# On_Board_Computer.net
KiCad netlist of a schematic drawn in EAGLE
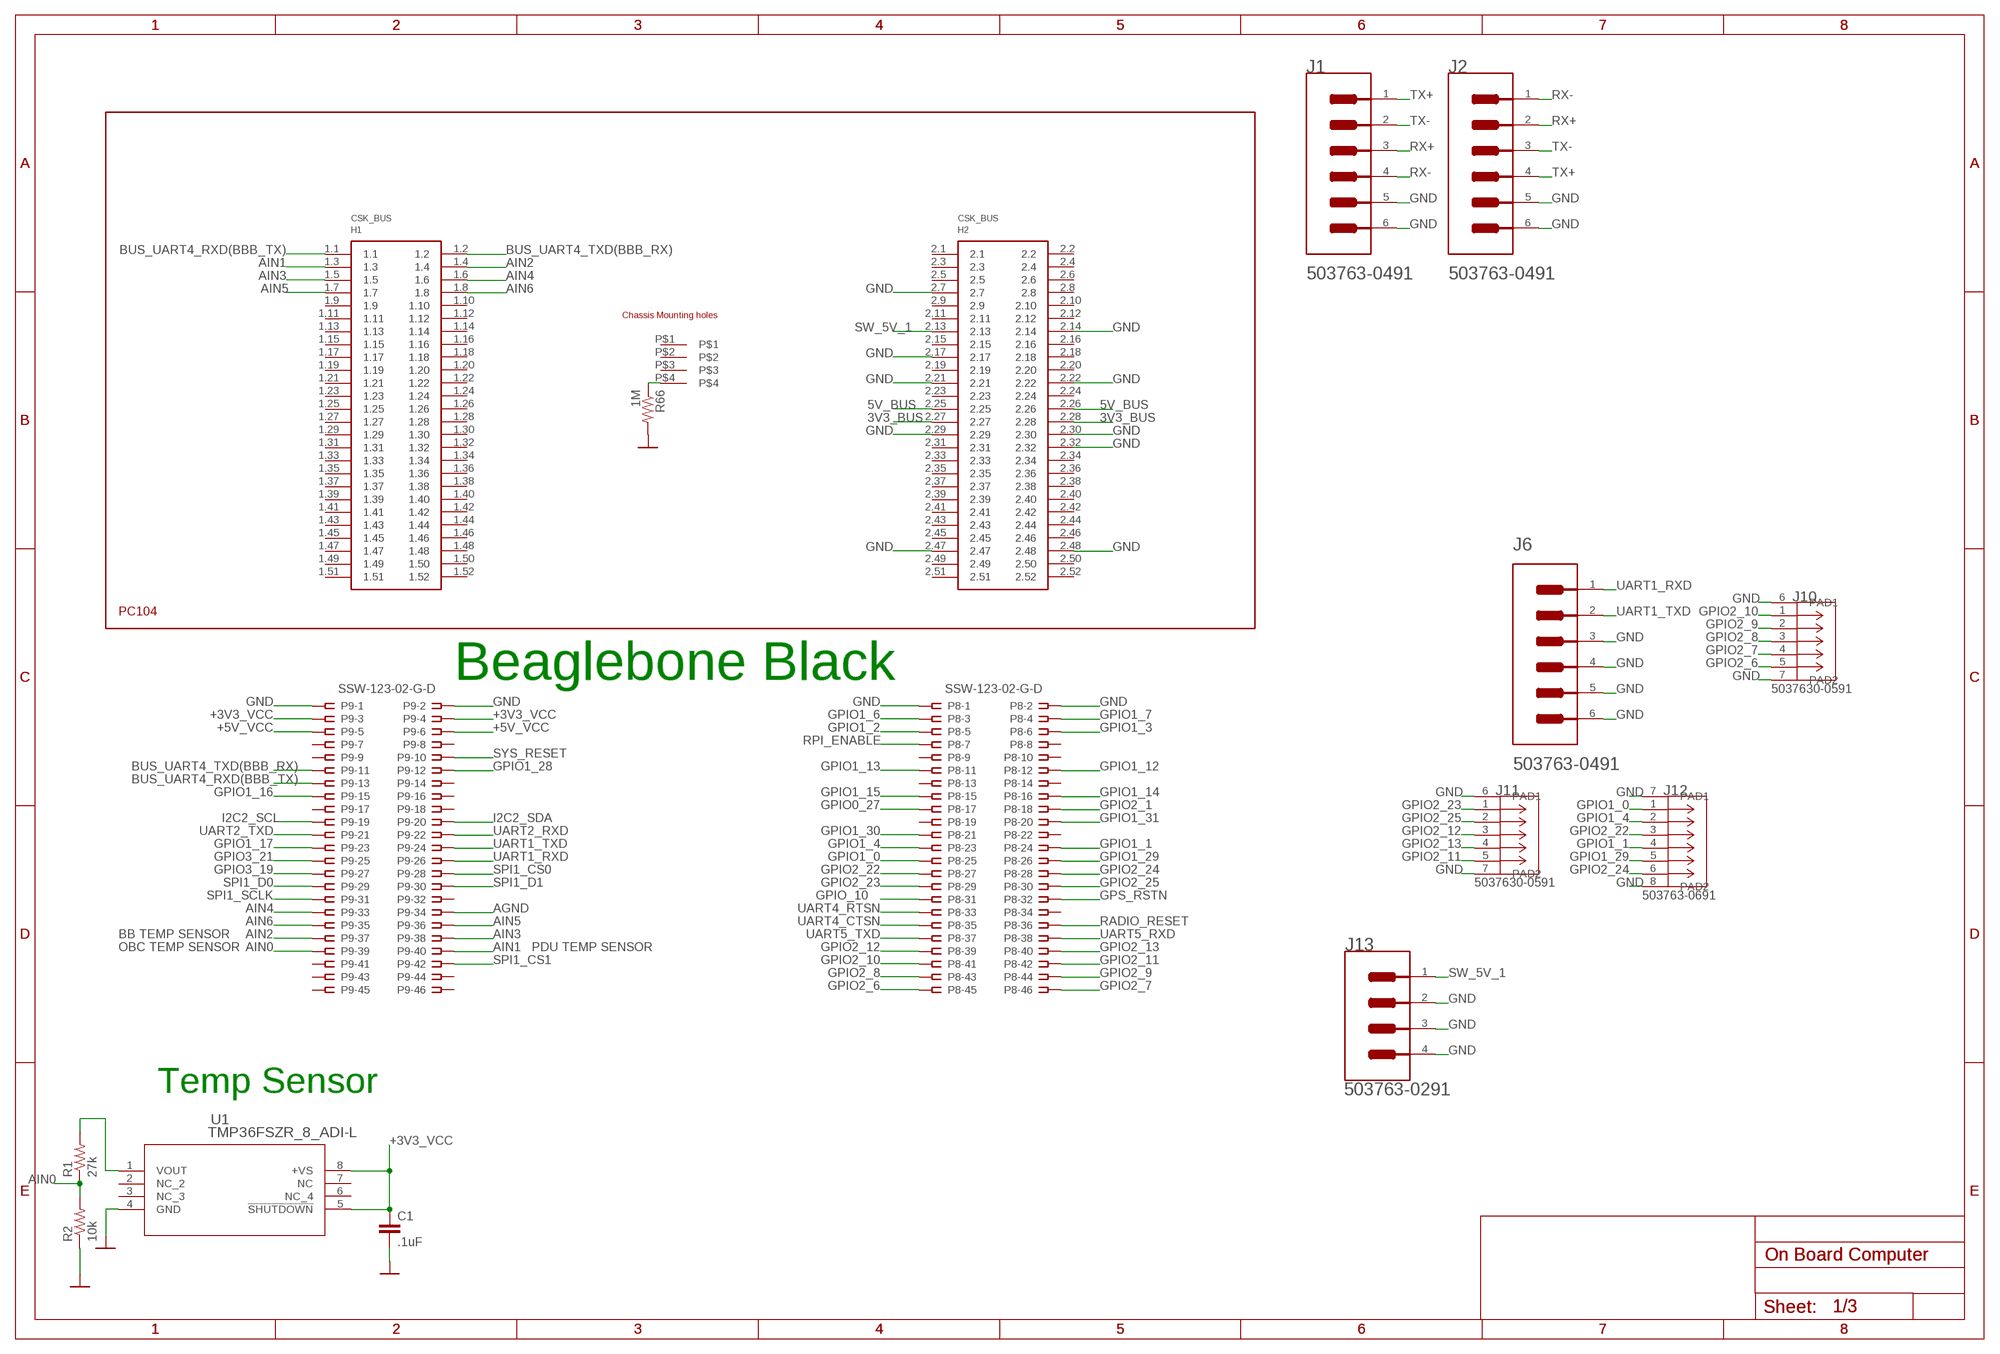
[diagram p0: schematic, sheet 1]
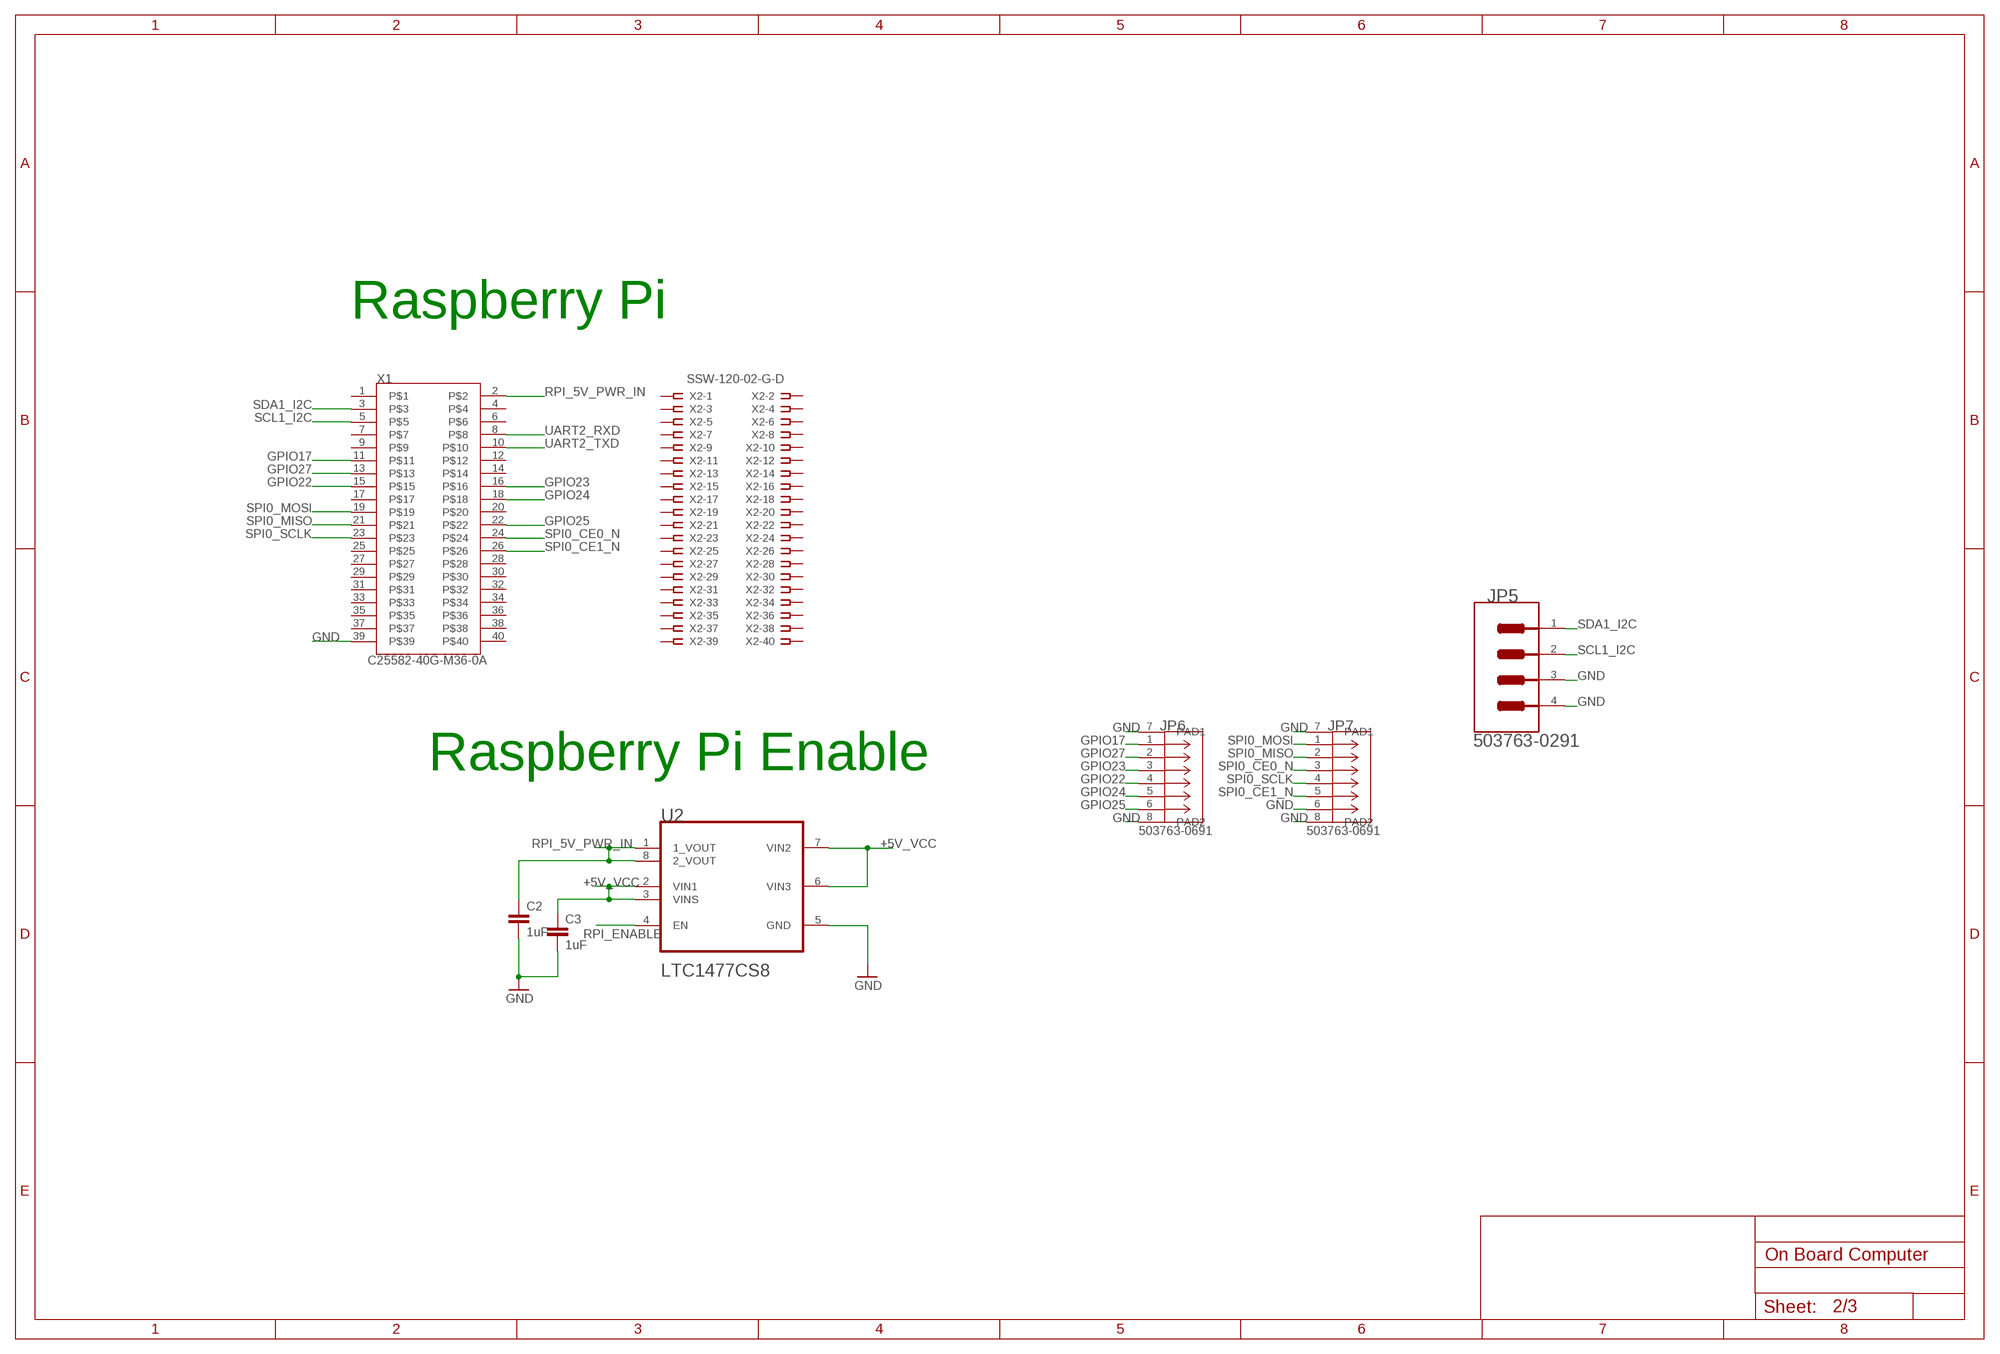
[diagram p1: schematic, sheet 2]
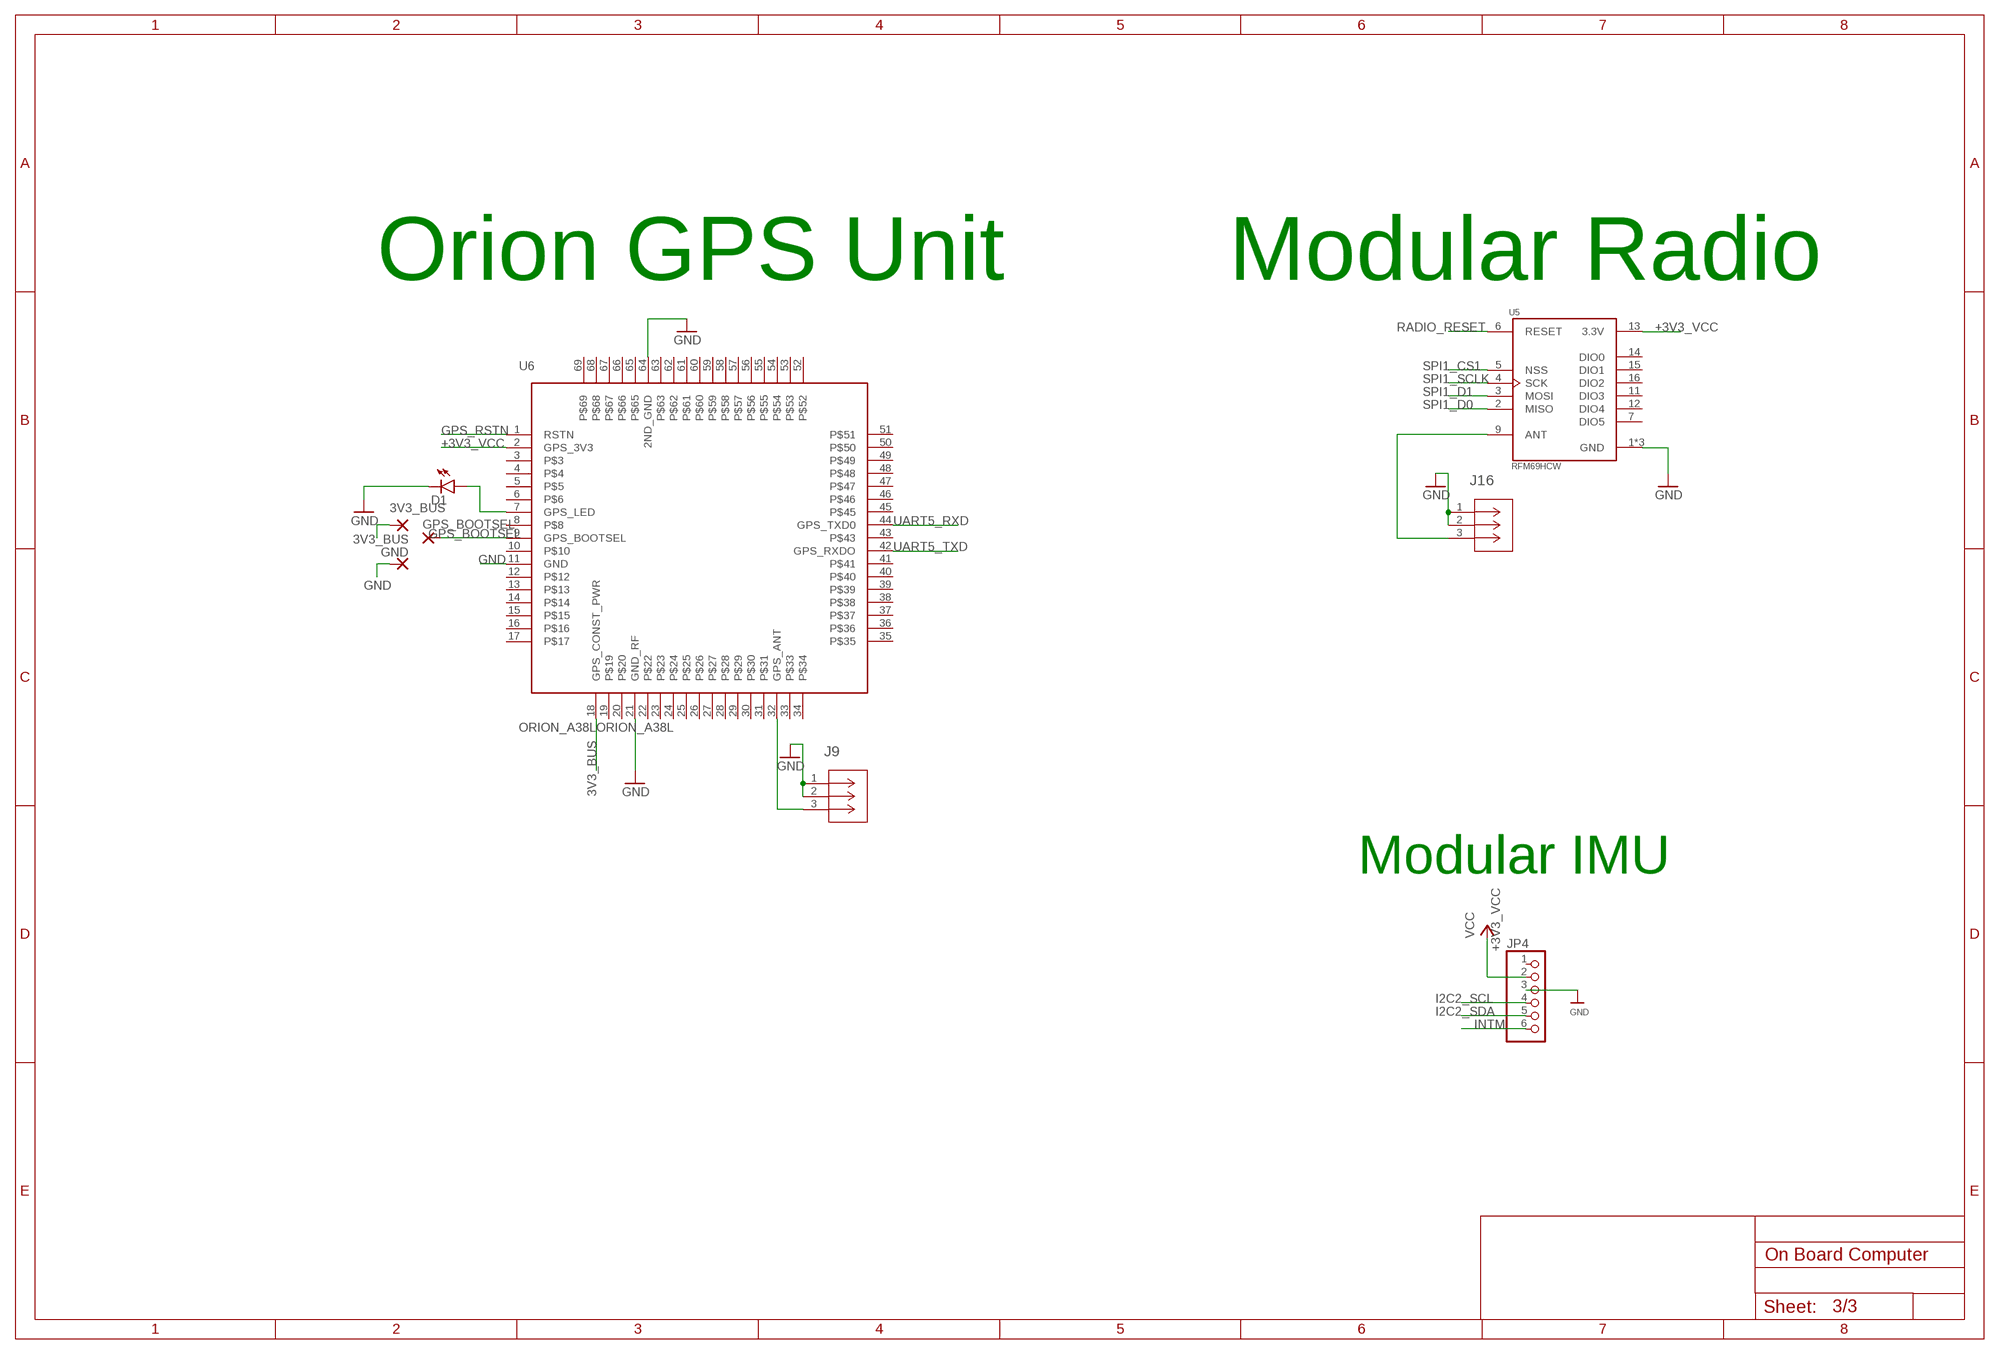
[diagram p2: schematic, sheet 3]

(export (version "E")
  (design (tool "Eeschema 10.0.6"))
  (components
    (comp (ref "C1")
      (value ".1uF")
      (footprint "eagle-import:0805")
      (libsource (lib "eagle-import") (part "CAP0805"))
    )
    (comp (ref "H1")
      (value "PC104_WCONN")
      (footprint "eagle-import:PC104_WCONN")
      (libsource (lib "eagle-import") (part "PC104_WCONN"))
    )
    (comp (ref "J1")
      (value "MOLEX_503763-0491MOLEX_503763-0491_0_0")
      (footprint "eagle-import:MOLEX_503763-0491_0")
      (fields
        (field (name "DIGIKEY_PART_NUMBER") "WM10655CT-ND")
        (field (name "MF") "Molex")
        (field (name "MOUSER_PART_NUMBER") "538-503763-0491")
      )
      (libsource (lib "eagle-import") (part "MOLEX_503763-0491MOLEX_503763-0491_0_0"))
    )
    (comp (ref "J2")
      (value "MOLEX_503763-0491MOLEX_503763-0491_0_0")
      (footprint "eagle-import:MOLEX_503763-0491_0")
      (fields
        (field (name "DIGIKEY_PART_NUMBER") "WM10655CT-ND")
        (field (name "MF") "Molex")
        (field (name "MOUSER_PART_NUMBER") "538-503763-0491")
      )
      (libsource (lib "eagle-import") (part "MOLEX_503763-0491MOLEX_503763-0491_0_0"))
    )
    (comp (ref "J6")
      (value "MOLEX_503763-0491MOLEX_503763-0491_0_0")
      (footprint "eagle-import:MOLEX_503763-0491_0")
      (fields
        (field (name "DIGIKEY_PART_NUMBER") "WM10655CT-ND")
        (field (name "MF") "Molex")
        (field (name "MOUSER_PART_NUMBER") "538-503763-0491")
      )
      (libsource (lib "eagle-import") (part "MOLEX_503763-0491MOLEX_503763-0491_0_0"))
    )
    (comp (ref "J10")
      (value "503763-0591")
      (footprint "eagle-import:CONN_5037630591_MOL")
      (fields (field (name "COPYRIGHT") "Copyright (C) 2018 Accelerated Designs. All rights reserved"))
      (libsource (lib "eagle-import") (part "503763-0591"))
    )
    (comp (ref "J11")
      (value "503763-0591")
      (footprint "eagle-import:CONN_5037630591_MOL")
      (fields (field (name "COPYRIGHT") "Copyright (C) 2018 Accelerated Designs. All rights reserved"))
      (libsource (lib "eagle-import") (part "503763-0591"))
    )
    (comp (ref "J12")
      (value "503763-0691")
      (footprint "eagle-import:CONN_503763-0691_MOL")
      (fields (field (name "COPYRIGHT") "Copyright (C) 2018 Accelerated Designs. All rights reserved"))
      (libsource (lib "eagle-import") (part "503763-0691"))
    )
    (comp (ref "J13")
      (value "MOLEX_503763-0291MOLEX_503763-0291_0_0")
      (footprint "eagle-import:MOLEX_503763-0291_0")
      (fields
        (field (name "DIGIKEY_PART_NUMBER") "WM10654CT-ND")
        (field (name "MF") "Molex")
        (field (name "MOUSER_PART_NUMBER") "538-503763-0291")
      )
      (libsource (lib "eagle-import") (part "MOLEX_503763-0291MOLEX_503763-0291_0_0"))
    )
    (comp (ref "P8")
      (value "SSW-123-02-G-D")
      (footprint "eagle-import:SSW-123-02-G-D")
      (fields (field (name "MF") "Samtec Inc."))
      (libsource (lib "eagle-import") (part "SSW-123-02-G-D"))
    )
    (comp (ref "P9")
      (value "SSW-123-02-G-D")
      (footprint "eagle-import:SSW-123-02-G-D")
      (fields (field (name "MF") "Samtec Inc."))
      (libsource (lib "eagle-import") (part "SSW-123-02-G-D"))
    )
    (comp (ref "R1")
      (value "27k")
      (footprint "eagle-import:0805")
      (libsource (lib "eagle-import") (part "RESISTOR0805-RES"))
    )
    (comp (ref "R2")
      (value "10k")
      (footprint "eagle-import:0805")
      (libsource (lib "eagle-import") (part "RESISTOR0805-RES"))
    )
    (comp (ref "R66")
      (value "1M")
      (footprint "eagle-import:0805")
      (libsource (lib "eagle-import") (part "RESISTOR0805-RES"))
    )
    (comp (ref "U1")
      (value "TMP36FSZR_8_ADI-L")
      (footprint "eagle-import:R_8_ADI-L")
      (fields
        (field (name "MANUFACTURER_PART_NUMBER") "TMP36FSZ")
        (field (name "COPYRIGHT") "Copyright (C) 2021 Ultra Librarian. All rights reserved.")
      )
      (libsource (lib "eagle-import") (part "TMP36FSZR_8_ADI-L"))
    )
    (comp (ref "3V3_BUS")
      (value "1,6/0,9")
      (footprint "eagle-import:1,6_0,9")
      (libsource (lib "eagle-import") (part "1,6/0,9"))
    )
    (comp (ref "D1")
      (value "LEDCHIP-LED0603")
      (footprint "eagle-import:CHIP-LED0603")
      (libsource (lib "eagle-import") (part "LEDCHIP-LED0603"))
    )
    (comp (ref "GND")
      (value "GND")
      (footprint "eagle-import:1,6_0,9")
      (libsource (lib "eagle-import") (part "1,6/0,9"))
    )
    (comp (ref "GPS_BOOTSEL")
      (value "1,6/0,9")
      (footprint "eagle-import:1,6_0,9")
      (libsource (lib "eagle-import") (part "1,6/0,9"))
    )
    (comp (ref "J9")
      (value "U.FL-R-SMT-1(01)")
      (footprint "eagle-import:CONN_-SMT-1(01)")
      (fields (field (name "COPYRIGHT") "Copyright (C) 2018 Accelerated Designs. All rights reserved"))
      (libsource (lib "eagle-import") (part "U.FL-R-SMT-1(01)"))
    )
    (comp (ref "J16")
      (value "U.FL-R-SMT-1(01)")
      (footprint "eagle-import:CONN_-SMT-1(01)")
      (fields (field (name "COPYRIGHT") "Copyright (C) 2018 Accelerated Designs. All rights reserved"))
      (libsource (lib "eagle-import") (part "U.FL-R-SMT-1(01)"))
    )
    (comp (ref "JP4")
      (value "HEADER-1X670MIL")
      (footprint "eagle-import:1X06_ROUND_70")
      (libsource (lib "eagle-import") (part "HEADER-1X670MIL"))
    )
    (comp (ref "U5")
      (value "RFM69HCW")
      (footprint "eagle-import:RFM69HCW")
      (fields (field (name "MF") "HOPERF") (field (name "MP") "RFM69HCW-315S2"))
      (libsource (lib "eagle-import") (part "RFM69HCW"))
    )
    (comp (ref "U6")
      (value "ORION_A38LORION_A38L")
      (footprint "eagle-import:ORION_A38L")
      (libsource (lib "eagle-import") (part "ORION_A38LORION_A38L"))
    )
    (comp (ref "C2")
      (value "1uF")
      (footprint "eagle-import:0805")
      (libsource (lib "eagle-import") (part "CAP0805"))
    )
    (comp (ref "C3")
      (value "1uF")
      (footprint "eagle-import:0805")
      (libsource (lib "eagle-import") (part "CAP0805"))
    )
    (comp (ref "JP5")
      (value "MOLEX_503763-0291MOLEX_503763-0291_0_0")
      (footprint "eagle-import:MOLEX_503763-0291_0")
      (fields
        (field (name "DIGIKEY_PART_NUMBER") "WM10654CT-ND")
        (field (name "MF") "Molex")
        (field (name "MOUSER_PART_NUMBER") "538-503763-0291")
      )
      (libsource (lib "eagle-import") (part "MOLEX_503763-0291MOLEX_503763-0291_0_0"))
    )
    (comp (ref "JP6")
      (value "503763-0691")
      (footprint "eagle-import:CONN_503763-0691_MOL")
      (fields (field (name "COPYRIGHT") "Copyright (C) 2018 Accelerated Designs. All rights reserved"))
      (libsource (lib "eagle-import") (part "503763-0691"))
    )
    (comp (ref "JP7")
      (value "503763-0691")
      (footprint "eagle-import:CONN_503763-0691_MOL")
      (fields (field (name "COPYRIGHT") "Copyright (C) 2018 Accelerated Designs. All rights reserved"))
      (libsource (lib "eagle-import") (part "503763-0691"))
    )
    (comp (ref "U2")
      (value "LTC1477CS8LINEAR_TECHNOLOGY_LTC1477CS8_0_2")
      (footprint "eagle-import:LINEAR_TECHNOLOGY_LTC1477CS8_2")
      (fields (field (name "MF") "Linear Technology") (field (name "MPN") "LTC1477CS8"))
      (libsource (lib "eagle-import") (part "LTC1477CS8LINEAR_TECHNOLOGY_LTC1477CS8_0_2"))
    )
    (comp (ref "X1")
      (value "C25582-40G-M36-0A")
      (footprint "eagle-import:ADAFRUIT_C25582-40G-M36-0A_0")
      (libsource (lib "eagle-import") (part "C25582-40G-M36-0A"))
    )
    (comp (ref "X2")
      (value "SSW-120-02-G-D")
      (footprint "eagle-import:SSW-120-02-G-D")
      (fields (field (name "MF") "Samtec Inc."))
      (libsource (lib "eagle-import") (part "SSW-120-02-G-D"))
    )
  )
  (nets
    (net (code "1") (name "+3V3_VCC") (class "Default")
      (node (ref "C1") (pin "1") (pinfunction "1_1") (pintype "passive"))
      (node (ref "JP4") (pin "2") (pinfunction "2_2") (pintype "passive"))
      (node (ref "P9") (pin "3") (pinfunction "1_3") (pintype "passive"))
      (node (ref "P9") (pin "4") (pinfunction "1_4") (pintype "passive"))
      (node (ref "U1") (pin "5") (pinfunction "~{SHUTDOWN}_5") (pintype "passive"))
      (node (ref "U1") (pin "8") (pinfunction "+VS_8") (pintype "power_in"))
      (node (ref "U5") (pin "13") (pinfunction "3.3V_13") (pintype "power_in"))
      (node (ref "U6") (pin "2") (pinfunction "GPS_3V3_2") (pintype "bidirectional"))
    )
    (net (code "2") (name "+5V_VCC") (class "Default")
      (node (ref "C3") (pin "1") (pinfunction "1_1") (pintype "passive"))
      (node (ref "P9") (pin "5") (pinfunction "1_5") (pintype "passive"))
      (node (ref "P9") (pin "6") (pinfunction "1_6") (pintype "passive"))
      (node (ref "U2") (pin "2") (pinfunction "VIN1_2") (pintype "power_in"))
      (node (ref "U2") (pin "3") (pinfunction "VINS_3") (pintype "power_in"))
      (node (ref "U2") (pin "6") (pinfunction "VIN3_6") (pintype "power_in"))
      (node (ref "U2") (pin "7") (pinfunction "VIN2_7") (pintype "power_in"))
    )
    (net (code "3") (name "3V3_BUS") (class "Default")
      (node (ref "3V3_BUS") (pin "1") (pinfunction "P_1") (pintype "passive"))
      (node (ref "H1") (pin "2.27") (pinfunction "2.27_2.27") (pintype "bidirectional"))
      (node (ref "H1") (pin "2.28") (pinfunction "2.28_2.28") (pintype "bidirectional"))
      (node (ref "U6") (pin "18") (pinfunction "GPS_CONST_PWR_18") (pintype "bidirectional"))
    )
    (net (code "4") (name "5V_BUS") (class "Default")
      (node (ref "H1") (pin "2.25") (pinfunction "2.25_2.25") (pintype "bidirectional"))
      (node (ref "H1") (pin "2.26") (pinfunction "2.26_2.26") (pintype "bidirectional"))
    )
    (net (code "5") (name "AGND") (class "Default")
      (node (ref "P9") (pin "34") (pinfunction "1_34") (pintype "passive"))
    )
    (net (code "6") (name "AIN0") (class "Default")
      (node (ref "P9") (pin "39") (pinfunction "1_39") (pintype "passive"))
      (node (ref "R1") (pin "1") (pinfunction "1_1") (pintype "passive"))
      (node (ref "R2") (pin "2") (pinfunction "2_2") (pintype "passive"))
    )
    (net (code "7") (name "AIN1") (class "Default")
      (node (ref "H1") (pin "1.3") (pinfunction "1.3_1.3") (pintype "bidirectional"))
      (node (ref "P9") (pin "40") (pinfunction "1_40") (pintype "passive"))
    )
    (net (code "8") (name "AIN2") (class "Default")
      (node (ref "H1") (pin "1.4") (pinfunction "1.4_1.4") (pintype "bidirectional"))
      (node (ref "P9") (pin "37") (pinfunction "1_37") (pintype "passive"))
    )
    (net (code "9") (name "AIN3") (class "Default")
      (node (ref "H1") (pin "1.5") (pinfunction "1.5_1.5") (pintype "bidirectional"))
      (node (ref "P9") (pin "38") (pinfunction "1_38") (pintype "passive"))
    )
    (net (code "10") (name "AIN4") (class "Default")
      (node (ref "H1") (pin "1.6") (pinfunction "1.6_1.6") (pintype "bidirectional"))
      (node (ref "P9") (pin "33") (pinfunction "1_33") (pintype "passive"))
    )
    (net (code "11") (name "AIN5") (class "Default")
      (node (ref "H1") (pin "1.7") (pinfunction "1.7_1.7") (pintype "bidirectional"))
      (node (ref "P9") (pin "36") (pinfunction "1_36") (pintype "passive"))
    )
    (net (code "12") (name "AIN6") (class "Default")
      (node (ref "H1") (pin "1.8") (pinfunction "1.8_1.8") (pintype "bidirectional"))
      (node (ref "P9") (pin "35") (pinfunction "1_35") (pintype "passive"))
    )
    (net (code "13") (name "BUS_UART4_RXD(BBB_TX)") (class "Default")
      (node (ref "H1") (pin "1.1") (pinfunction "1.1_1.1") (pintype "bidirectional"))
      (node (ref "P9") (pin "13") (pinfunction "1_13") (pintype "passive"))
    )
    (net (code "14") (name "BUS_UART4_TXD(BBB_RX)") (class "Default")
      (node (ref "H1") (pin "1.2") (pinfunction "1.2_1.2") (pintype "bidirectional"))
      (node (ref "P9") (pin "11") (pinfunction "1_11") (pintype "passive"))
    )
    (net (code "15") (name "GND") (class "Default")
      (node (ref "C1") (pin "2") (pinfunction "2_2") (pintype "passive"))
      (node (ref "C2") (pin "2") (pinfunction "2_2") (pintype "passive"))
      (node (ref "C3") (pin "2") (pinfunction "2_2") (pintype "passive"))
      (node (ref "D1") (pin "C") (pinfunction "C_C") (pintype "passive"))
      (node (ref "GND") (pin "1") (pinfunction "P_1") (pintype "passive"))
      (node (ref "H1") (pin "2.14") (pinfunction "2.14_2.14") (pintype "bidirectional"))
      (node (ref "H1") (pin "2.17") (pinfunction "2.17_2.17") (pintype "bidirectional"))
      (node (ref "H1") (pin "2.21") (pinfunction "2.21_2.21") (pintype "bidirectional"))
      (node (ref "H1") (pin "2.22") (pinfunction "2.22_2.22") (pintype "bidirectional"))
      (node (ref "H1") (pin "2.29") (pinfunction "2.29_2.29") (pintype "bidirectional"))
      (node (ref "H1") (pin "2.30") (pinfunction "2.30_2.30") (pintype "bidirectional"))
      (node (ref "H1") (pin "2.32") (pinfunction "2.32_2.32") (pintype "bidirectional"))
      (node (ref "H1") (pin "2.47") (pinfunction "2.47_2.47") (pintype "bidirectional"))
      (node (ref "H1") (pin "2.48") (pinfunction "2.48_2.48") (pintype "bidirectional"))
      (node (ref "H1") (pin "2.7") (pinfunction "2.7_2.7") (pintype "bidirectional"))
      (node (ref "J1") (pin "5") (pinfunction "MNT_1_5") (pintype "passive"))
      (node (ref "J1") (pin "6") (pinfunction "MNT_2_6") (pintype "passive"))
      (node (ref "J10") (pin "6") (pinfunction "PAD1_6") (pintype "bidirectional"))
      (node (ref "J10") (pin "7") (pinfunction "PAD2_7") (pintype "bidirectional"))
      (node (ref "J11") (pin "6") (pinfunction "PAD1_6") (pintype "bidirectional"))
      (node (ref "J11") (pin "7") (pinfunction "PAD2_7") (pintype "bidirectional"))
      (node (ref "J12") (pin "7") (pinfunction "PAD1_7") (pintype "bidirectional"))
      (node (ref "J12") (pin "8") (pinfunction "PAD2_8") (pintype "bidirectional"))
      (node (ref "J13") (pin "2") (pinfunction "2_2") (pintype "bidirectional"))
      (node (ref "J13") (pin "3") (pinfunction "MNT_1_3") (pintype "bidirectional"))
      (node (ref "J13") (pin "4") (pinfunction "MNT_2_4") (pintype "bidirectional"))
      (node (ref "J16") (pin "1") (pinfunction "1_1") (pintype "passive"))
      (node (ref "J16") (pin "2") (pinfunction "2_2") (pintype "passive"))
      (node (ref "J2") (pin "5") (pinfunction "MNT_1_5") (pintype "passive"))
      (node (ref "J2") (pin "6") (pinfunction "MNT_2_6") (pintype "passive"))
      (node (ref "J6") (pin "3") (pinfunction "3_3") (pintype "passive"))
      (node (ref "J6") (pin "4") (pinfunction "4_4") (pintype "passive"))
      (node (ref "J6") (pin "5") (pinfunction "MNT_1_5") (pintype "passive"))
      (node (ref "J6") (pin "6") (pinfunction "MNT_2_6") (pintype "passive"))
      (node (ref "J9") (pin "1") (pinfunction "1_1") (pintype "passive"))
      (node (ref "J9") (pin "2") (pinfunction "2_2") (pintype "passive"))
      (node (ref "JP4") (pin "3") (pinfunction "3_3") (pintype "passive"))
      (node (ref "JP5") (pin "3") (pinfunction "MNT_1_3") (pintype "bidirectional"))
      (node (ref "JP5") (pin "4") (pinfunction "MNT_2_4") (pintype "bidirectional"))
      (node (ref "JP6") (pin "7") (pinfunction "PAD1_7") (pintype "bidirectional"))
      (node (ref "JP6") (pin "8") (pinfunction "PAD2_8") (pintype "bidirectional"))
      (node (ref "JP7") (pin "6") (pinfunction "6_6") (pintype "passive"))
      (node (ref "JP7") (pin "7") (pinfunction "PAD1_7") (pintype "bidirectional"))
      (node (ref "JP7") (pin "8") (pinfunction "PAD2_8") (pintype "bidirectional"))
      (node (ref "P8") (pin "1") (pinfunction "1_1") (pintype "passive"))
      (node (ref "P8") (pin "2") (pinfunction "1_2") (pintype "passive"))
      (node (ref "P9") (pin "1") (pinfunction "1_1") (pintype "passive"))
      (node (ref "P9") (pin "2") (pinfunction "1_2") (pintype "passive"))
      (node (ref "R2") (pin "1") (pinfunction "1_1") (pintype "passive"))
      (node (ref "R66") (pin "2") (pinfunction "2_2") (pintype "passive"))
      (node (ref "U1") (pin "4") (pinfunction "GND_4") (pintype "passive"))
      (node (ref "U2") (pin "5") (pinfunction "GND_5") (pintype "power_in"))
      (node (ref "U5") (pin "1") (pinfunction "GND_1") (pintype "power_in"))
      (node (ref "U5") (pin "10") (pinfunction "GND_10") (pintype "power_in"))
      (node (ref "U5") (pin "8") (pinfunction "GND_8") (pintype "power_in"))
      (node (ref "U6") (pin "11") (pinfunction "GND_11") (pintype "bidirectional"))
      (node (ref "U6") (pin "21") (pinfunction "GND_RF_21") (pintype "bidirectional"))
      (node (ref "U6") (pin "64") (pinfunction "2ND_GND_64") (pintype "bidirectional"))
      (node (ref "X1") (pin "39") (pinfunction "P$39_39") (pintype "bidirectional"))
    )
    (net (code "16") (name "GPIO0_27") (class "Default")
      (node (ref "P8") (pin "17") (pinfunction "1_17") (pintype "passive"))
    )
    (net (code "17") (name "GPIO1_0") (class "Default")
      (node (ref "J12") (pin "1") (pinfunction "1_1") (pintype "passive"))
      (node (ref "P8") (pin "25") (pinfunction "1_25") (pintype "passive"))
    )
    (net (code "18") (name "GPIO1_1") (class "Default")
      (node (ref "J12") (pin "4") (pinfunction "4_4") (pintype "passive"))
      (node (ref "P8") (pin "24") (pinfunction "1_24") (pintype "passive"))
    )
    (net (code "19") (name "GPIO1_2") (class "Default")
      (node (ref "P8") (pin "5") (pinfunction "1_5") (pintype "passive"))
    )
    (net (code "20") (name "GPIO1_3") (class "Default")
      (node (ref "P8") (pin "6") (pinfunction "1_6") (pintype "passive"))
    )
    (net (code "21") (name "GPIO1_4") (class "Default")
      (node (ref "J12") (pin "2") (pinfunction "2_2") (pintype "passive"))
      (node (ref "P8") (pin "23") (pinfunction "1_23") (pintype "passive"))
    )
    (net (code "22") (name "GPIO1_6") (class "Default")
      (node (ref "P8") (pin "3") (pinfunction "1_3") (pintype "passive"))
    )
    (net (code "23") (name "GPIO1_7") (class "Default")
      (node (ref "P8") (pin "4") (pinfunction "1_4") (pintype "passive"))
    )
    (net (code "24") (name "GPIO1_12") (class "Default")
      (node (ref "P8") (pin "12") (pinfunction "1_12") (pintype "passive"))
    )
    (net (code "25") (name "GPIO1_13") (class "Default")
      (node (ref "P8") (pin "11") (pinfunction "1_11") (pintype "passive"))
    )
    (net (code "26") (name "GPIO1_14") (class "Default")
      (node (ref "P8") (pin "16") (pinfunction "1_16") (pintype "passive"))
    )
    (net (code "27") (name "GPIO1_15") (class "Default")
      (node (ref "P8") (pin "15") (pinfunction "1_15") (pintype "passive"))
    )
    (net (code "28") (name "GPIO1_16") (class "Default")
      (node (ref "P9") (pin "15") (pinfunction "1_15") (pintype "passive"))
    )
    (net (code "29") (name "GPIO1_17") (class "Default")
      (node (ref "P9") (pin "23") (pinfunction "1_23") (pintype "passive"))
    )
    (net (code "30") (name "GPIO1_28") (class "Default")
      (node (ref "P9") (pin "12") (pinfunction "1_12") (pintype "passive"))
    )
    (net (code "31") (name "GPIO1_29") (class "Default")
      (node (ref "J12") (pin "5") (pinfunction "5_5") (pintype "passive"))
      (node (ref "P8") (pin "26") (pinfunction "1_26") (pintype "passive"))
    )
    (net (code "32") (name "GPIO1_30") (class "Default")
      (node (ref "P8") (pin "21") (pinfunction "1_21") (pintype "passive"))
    )
    (net (code "33") (name "GPIO1_31") (class "Default")
      (node (ref "P8") (pin "20") (pinfunction "1_20") (pintype "passive"))
    )
    (net (code "34") (name "GPIO2_1") (class "Default")
      (node (ref "P8") (pin "18") (pinfunction "1_18") (pintype "passive"))
    )
    (net (code "35") (name "GPIO2_6") (class "Default")
      (node (ref "J10") (pin "5") (pinfunction "5_5") (pintype "passive"))
      (node (ref "P8") (pin "45") (pinfunction "1_45") (pintype "passive"))
    )
    (net (code "36") (name "GPIO2_7") (class "Default")
      (node (ref "J10") (pin "4") (pinfunction "4_4") (pintype "passive"))
      (node (ref "P8") (pin "46") (pinfunction "1_46") (pintype "passive"))
    )
    (net (code "37") (name "GPIO2_8") (class "Default")
      (node (ref "J10") (pin "3") (pinfunction "3_3") (pintype "passive"))
      (node (ref "P8") (pin "43") (pinfunction "1_43") (pintype "passive"))
    )
    (net (code "38") (name "GPIO2_9") (class "Default")
      (node (ref "J10") (pin "2") (pinfunction "2_2") (pintype "passive"))
      (node (ref "P8") (pin "44") (pinfunction "1_44") (pintype "passive"))
    )
    (net (code "39") (name "GPIO2_10") (class "Default")
      (node (ref "J10") (pin "1") (pinfunction "1_1") (pintype "passive"))
      (node (ref "P8") (pin "41") (pinfunction "1_41") (pintype "passive"))
    )
    (net (code "40") (name "GPIO2_11") (class "Default")
      (node (ref "J11") (pin "5") (pinfunction "5_5") (pintype "passive"))
      (node (ref "P8") (pin "42") (pinfunction "1_42") (pintype "passive"))
    )
    (net (code "41") (name "GPIO2_12") (class "Default")
      (node (ref "J11") (pin "3") (pinfunction "3_3") (pintype "passive"))
      (node (ref "P8") (pin "39") (pinfunction "1_39") (pintype "passive"))
    )
    (net (code "42") (name "GPIO2_13") (class "Default")
      (node (ref "J11") (pin "4") (pinfunction "4_4") (pintype "passive"))
      (node (ref "P8") (pin "40") (pinfunction "1_40") (pintype "passive"))
    )
    (net (code "43") (name "GPIO2_22") (class "Default")
      (node (ref "J12") (pin "3") (pinfunction "3_3") (pintype "passive"))
      (node (ref "P8") (pin "27") (pinfunction "1_27") (pintype "passive"))
    )
    (net (code "44") (name "GPIO2_23") (class "Default")
      (node (ref "J11") (pin "1") (pinfunction "1_1") (pintype "passive"))
      (node (ref "P8") (pin "29") (pinfunction "1_29") (pintype "passive"))
    )
    (net (code "45") (name "GPIO2_24") (class "Default")
      (node (ref "J12") (pin "6") (pinfunction "6_6") (pintype "passive"))
      (node (ref "P8") (pin "28") (pinfunction "1_28") (pintype "passive"))
    )
    (net (code "46") (name "GPIO2_25") (class "Default")
      (node (ref "J11") (pin "2") (pinfunction "2_2") (pintype "passive"))
      (node (ref "P8") (pin "30") (pinfunction "1_30") (pintype "passive"))
    )
    (net (code "47") (name "GPIO3_19") (class "Default")
      (node (ref "P9") (pin "27") (pinfunction "1_27") (pintype "passive"))
    )
    (net (code "48") (name "GPIO3_21") (class "Default")
      (node (ref "P9") (pin "25") (pinfunction "1_25") (pintype "passive"))
    )
    (net (code "49") (name "GPIO17") (class "Default")
      (node (ref "JP6") (pin "1") (pinfunction "1_1") (pintype "passive"))
      (node (ref "X1") (pin "11") (pinfunction "P$11_11") (pintype "bidirectional"))
    )
    (net (code "50") (name "GPIO22") (class "Default")
      (node (ref "JP6") (pin "4") (pinfunction "4_4") (pintype "passive"))
      (node (ref "X1") (pin "15") (pinfunction "P$15_15") (pintype "bidirectional"))
    )
    (net (code "51") (name "GPIO23") (class "Default")
      (node (ref "JP6") (pin "3") (pinfunction "3_3") (pintype "passive"))
      (node (ref "X1") (pin "16") (pinfunction "P$16_16") (pintype "bidirectional"))
    )
    (net (code "52") (name "GPIO24") (class "Default")
      (node (ref "JP6") (pin "5") (pinfunction "5_5") (pintype "passive"))
      (node (ref "X1") (pin "18") (pinfunction "P$18_18") (pintype "bidirectional"))
    )
    (net (code "53") (name "GPIO25") (class "Default")
      (node (ref "JP6") (pin "6") (pinfunction "6_6") (pintype "passive"))
      (node (ref "X1") (pin "22") (pinfunction "P$22_22") (pintype "bidirectional"))
    )
    (net (code "54") (name "GPIO27") (class "Default")
      (node (ref "JP6") (pin "2") (pinfunction "2_2") (pintype "passive"))
      (node (ref "X1") (pin "13") (pinfunction "P$13_13") (pintype "bidirectional"))
    )
    (net (code "55") (name "GPIO_10") (class "Default")
      (node (ref "P8") (pin "31") (pinfunction "1_31") (pintype "passive"))
    )
    (net (code "56") (name "GPS_BOOTSEL") (class "Default")
      (node (ref "GPS_BOOTSEL") (pin "1") (pinfunction "P_1") (pintype "passive"))
      (node (ref "U6") (pin "9") (pinfunction "GPS_BOOTSEL_9") (pintype "bidirectional"))
    )
    (net (code "57") (name "GPS_RSTN") (class "Default")
      (node (ref "P8") (pin "32") (pinfunction "1_32") (pintype "passive"))
      (node (ref "U6") (pin "1") (pinfunction "RSTN_1") (pintype "bidirectional"))
    )
    (net (code "58") (name "I2C2_SCL") (class "Default")
      (node (ref "JP4") (pin "4") (pinfunction "4_4") (pintype "passive"))
      (node (ref "P9") (pin "19") (pinfunction "1_19") (pintype "passive"))
    )
    (net (code "59") (name "I2C2_SDA") (class "Default")
      (node (ref "JP4") (pin "5") (pinfunction "5_5") (pintype "passive"))
      (node (ref "P9") (pin "20") (pinfunction "1_20") (pintype "passive"))
    )
    (net (code "60") (name "INTM") (class "Default")
      (node (ref "JP4") (pin "6") (pinfunction "6_6") (pintype "passive"))
    )
    (net (code "61") (name "Net-(H1-PadP$4)") (class "Default")
      (node (ref "H1") (pin "P$4") (pinfunction "P$4_P$4") (pintype "bidirectional"))
      (node (ref "R66") (pin "1") (pinfunction "1_1") (pintype "passive"))
    )
    (net (code "62") (name "Net-(U1-VOUT)") (class "Default")
      (node (ref "R1") (pin "2") (pinfunction "2_2") (pintype "passive"))
      (node (ref "U1") (pin "1") (pinfunction "VOUT_1") (pintype "output"))
    )
    (net (code "63") (name "Net-(U5-ANT)") (class "Default")
      (node (ref "J16") (pin "3") (pinfunction "3_3") (pintype "passive"))
      (node (ref "U5") (pin "9") (pinfunction "ANT_9") (pintype "bidirectional"))
    )
    (net (code "64") (name "Net-(U6-GPS_ANT)") (class "Default")
      (node (ref "J9") (pin "3") (pinfunction "3_3") (pintype "passive"))
      (node (ref "U6") (pin "32") (pinfunction "GPS_ANT_32") (pintype "bidirectional"))
    )
    (net (code "65") (name "Net-(U6-GPS_LED)") (class "Default")
      (node (ref "D1") (pin "A") (pinfunction "A_A") (pintype "passive"))
      (node (ref "U6") (pin "7") (pinfunction "GPS_LED_7") (pintype "bidirectional"))
    )
    (net (code "66") (name "RADIO_RESET") (class "Default")
      (node (ref "P8") (pin "36") (pinfunction "1_36") (pintype "passive"))
      (node (ref "U5") (pin "6") (pinfunction "RESET_6") (pintype "bidirectional"))
    )
    (net (code "67") (name "RPI_5V_PWR_IN") (class "Default")
      (node (ref "C2") (pin "1") (pinfunction "1_1") (pintype "passive"))
      (node (ref "U2") (pin "1") (pinfunction "1_VOUT_1") (pintype "power_in"))
      (node (ref "U2") (pin "8") (pinfunction "2_VOUT_8") (pintype "power_in"))
      (node (ref "X1") (pin "2") (pinfunction "P$2_2") (pintype "bidirectional"))
    )
    (net (code "68") (name "RPI_ENABLE") (class "Default")
      (node (ref "P8") (pin "7") (pinfunction "1_7") (pintype "passive"))
      (node (ref "U2") (pin "4") (pinfunction "EN_4") (pintype "input"))
    )
    (net (code "69") (name "RX+") (class "Default")
      (node (ref "J1") (pin "3") (pinfunction "3_3") (pintype "passive"))
      (node (ref "J2") (pin "2") (pinfunction "2_2") (pintype "passive"))
    )
    (net (code "70") (name "RX-") (class "Default")
      (node (ref "J1") (pin "4") (pinfunction "4_4") (pintype "passive"))
      (node (ref "J2") (pin "1") (pinfunction "1_1") (pintype "passive"))
    )
    (net (code "71") (name "SCL1_I2C") (class "Default")
      (node (ref "JP5") (pin "2") (pinfunction "2_2") (pintype "bidirectional"))
      (node (ref "X1") (pin "5") (pinfunction "P$5_5") (pintype "bidirectional"))
    )
    (net (code "72") (name "SDA1_I2C") (class "Default")
      (node (ref "JP5") (pin "1") (pinfunction "1_1") (pintype "bidirectional"))
      (node (ref "X1") (pin "3") (pinfunction "P$3_3") (pintype "bidirectional"))
    )
    (net (code "73") (name "SPI0_CE0_N") (class "Default")
      (node (ref "JP7") (pin "3") (pinfunction "3_3") (pintype "passive"))
      (node (ref "X1") (pin "24") (pinfunction "P$24_24") (pintype "bidirectional"))
    )
    (net (code "74") (name "SPI0_CE1_N") (class "Default")
      (node (ref "JP7") (pin "5") (pinfunction "5_5") (pintype "passive"))
      (node (ref "X1") (pin "26") (pinfunction "P$26_26") (pintype "bidirectional"))
    )
    (net (code "75") (name "SPI0_MISO") (class "Default")
      (node (ref "JP7") (pin "2") (pinfunction "2_2") (pintype "passive"))
      (node (ref "X1") (pin "21") (pinfunction "P$21_21") (pintype "bidirectional"))
    )
    (net (code "76") (name "SPI0_MOSI") (class "Default")
      (node (ref "JP7") (pin "1") (pinfunction "1_1") (pintype "passive"))
      (node (ref "X1") (pin "19") (pinfunction "P$19_19") (pintype "bidirectional"))
    )
    (net (code "77") (name "SPI0_SCLK") (class "Default")
      (node (ref "JP7") (pin "4") (pinfunction "4_4") (pintype "passive"))
      (node (ref "X1") (pin "23") (pinfunction "P$23_23") (pintype "bidirectional"))
    )
    (net (code "78") (name "SPI1_CS0") (class "Default")
      (node (ref "P9") (pin "28") (pinfunction "1_28") (pintype "passive"))
    )
    (net (code "79") (name "SPI1_CS1") (class "Default")
      (node (ref "P9") (pin "42") (pinfunction "1_42") (pintype "passive"))
      (node (ref "U5") (pin "5") (pinfunction "NSS_5") (pintype "input"))
    )
    (net (code "80") (name "SPI1_D0") (class "Default")
      (node (ref "P9") (pin "29") (pinfunction "1_29") (pintype "passive"))
      (node (ref "U5") (pin "2") (pinfunction "MISO_2") (pintype "input"))
    )
    (net (code "81") (name "SPI1_D1") (class "Default")
      (node (ref "P9") (pin "30") (pinfunction "1_30") (pintype "passive"))
      (node (ref "U5") (pin "3") (pinfunction "MOSI_3") (pintype "output"))
    )
    (net (code "82") (name "SPI1_SCLK") (class "Default")
      (node (ref "P9") (pin "31") (pinfunction "1_31") (pintype "passive"))
      (node (ref "U5") (pin "4") (pinfunction "SCK_4") (pintype "input"))
    )
    (net (code "83") (name "SW_5V_1") (class "Default")
      (node (ref "H1") (pin "2.13") (pinfunction "2.13_2.13") (pintype "bidirectional"))
      (node (ref "J13") (pin "1") (pinfunction "1_1") (pintype "bidirectional"))
    )
    (net (code "84") (name "SYS_RESET") (class "Default")
      (node (ref "P9") (pin "10") (pinfunction "1_10") (pintype "passive"))
    )
    (net (code "85") (name "TX+") (class "Default")
      (node (ref "J1") (pin "1") (pinfunction "1_1") (pintype "passive"))
      (node (ref "J2") (pin "4") (pinfunction "4_4") (pintype "passive"))
    )
    (net (code "86") (name "TX-") (class "Default")
      (node (ref "J1") (pin "2") (pinfunction "2_2") (pintype "passive"))
      (node (ref "J2") (pin "3") (pinfunction "3_3") (pintype "passive"))
    )
    (net (code "87") (name "UART1_RXD") (class "Default")
      (node (ref "J6") (pin "1") (pinfunction "1_1") (pintype "passive"))
      (node (ref "P9") (pin "26") (pinfunction "1_26") (pintype "passive"))
    )
    (net (code "88") (name "UART1_TXD") (class "Default")
      (node (ref "J6") (pin "2") (pinfunction "2_2") (pintype "passive"))
      (node (ref "P9") (pin "24") (pinfunction "1_24") (pintype "passive"))
    )
    (net (code "89") (name "UART2_RXD") (class "Default")
      (node (ref "P9") (pin "22") (pinfunction "1_22") (pintype "passive"))
      (node (ref "X1") (pin "8") (pinfunction "P$8_8") (pintype "bidirectional"))
    )
    (net (code "90") (name "UART2_TXD") (class "Default")
      (node (ref "P9") (pin "21") (pinfunction "1_21") (pintype "passive"))
      (node (ref "X1") (pin "10") (pinfunction "P$10_10") (pintype "bidirectional"))
    )
    (net (code "91") (name "UART4_CTSN") (class "Default")
      (node (ref "P8") (pin "35") (pinfunction "1_35") (pintype "passive"))
    )
    (net (code "92") (name "UART4_RTSN") (class "Default")
      (node (ref "P8") (pin "33") (pinfunction "1_33") (pintype "passive"))
    )
    (net (code "93") (name "UART5_RXD") (class "Default")
      (node (ref "P8") (pin "38") (pinfunction "1_38") (pintype "passive"))
      (node (ref "U6") (pin "44") (pinfunction "GPS_TXD0_44") (pintype "output"))
    )
    (net (code "94") (name "UART5_TXD") (class "Default")
      (node (ref "P8") (pin "37") (pinfunction "1_37") (pintype "passive"))
      (node (ref "U6") (pin "42") (pinfunction "GPS_RXDO_42") (pintype "input"))
    )
    (net (code "95") (name "unconnected-(H1-Pad1.9)") (class "Default")
      (node (ref "H1") (pin "1.9") (pinfunction "1.9_1.9") (pintype "bidirectional"))
    )
    (net (code "96") (name "unconnected-(H1-Pad1.10)") (class "Default")
      (node (ref "H1") (pin "1.10") (pinfunction "1.10_1.10") (pintype "bidirectional"))
    )
    (net (code "97") (name "unconnected-(H1-Pad1.11)") (class "Default")
      (node (ref "H1") (pin "1.11") (pinfunction "1.11_1.11") (pintype "bidirectional"))
    )
    (net (code "98") (name "unconnected-(H1-Pad1.12)") (class "Default")
      (node (ref "H1") (pin "1.12") (pinfunction "1.12_1.12") (pintype "bidirectional"))
    )
    (net (code "99") (name "unconnected-(H1-Pad1.13)") (class "Default")
      (node (ref "H1") (pin "1.13") (pinfunction "1.13_1.13") (pintype "bidirectional"))
    )
    (net (code "100") (name "unconnected-(H1-Pad1.14)") (class "Default")
      (node (ref "H1") (pin "1.14") (pinfunction "1.14_1.14") (pintype "bidirectional"))
    )
    (net (code "101") (name "unconnected-(H1-Pad1.15)") (class "Default")
      (node (ref "H1") (pin "1.15") (pinfunction "1.15_1.15") (pintype "bidirectional"))
    )
    (net (code "102") (name "unconnected-(H1-Pad1.16)") (class "Default")
      (node (ref "H1") (pin "1.16") (pinfunction "1.16_1.16") (pintype "bidirectional"))
    )
    (net (code "103") (name "unconnected-(H1-Pad1.17)") (class "Default")
      (node (ref "H1") (pin "1.17") (pinfunction "1.17_1.17") (pintype "bidirectional"))
    )
    (net (code "104") (name "unconnected-(H1-Pad1.18)") (class "Default")
      (node (ref "H1") (pin "1.18") (pinfunction "1.18_1.18") (pintype "bidirectional"))
    )
    (net (code "105") (name "unconnected-(H1-Pad1.19)") (class "Default")
      (node (ref "H1") (pin "1.19") (pinfunction "1.19_1.19") (pintype "bidirectional"))
    )
    (net (code "106") (name "unconnected-(H1-Pad1.20)") (class "Default")
      (node (ref "H1") (pin "1.20") (pinfunction "1.20_1.20") (pintype "bidirectional"))
    )
    (net (code "107") (name "unconnected-(H1-Pad1.21)") (class "Default")
      (node (ref "H1") (pin "1.21") (pinfunction "1.21_1.21") (pintype "bidirectional"))
    )
    (net (code "108") (name "unconnected-(H1-Pad1.22)") (class "Default")
      (node (ref "H1") (pin "1.22") (pinfunction "1.22_1.22") (pintype "bidirectional"))
    )
    (net (code "109") (name "unconnected-(H1-Pad1.23)") (class "Default")
      (node (ref "H1") (pin "1.23") (pinfunction "1.23_1.23") (pintype "bidirectional"))
    )
    (net (code "110") (name "unconnected-(H1-Pad1.24)") (class "Default")
      (node (ref "H1") (pin "1.24") (pinfunction "1.24_1.24") (pintype "bidirectional"))
    )
    (net (code "111") (name "unconnected-(H1-Pad1.25)") (class "Default")
      (node (ref "H1") (pin "1.25") (pinfunction "1.25_1.25") (pintype "bidirectional"))
    )
    (net (code "112") (name "unconnected-(H1-Pad1.26)") (class "Default")
      (node (ref "H1") (pin "1.26") (pinfunction "1.26_1.26") (pintype "bidirectional"))
    )
    (net (code "113") (name "unconnected-(H1-Pad1.27)") (class "Default")
      (node (ref "H1") (pin "1.27") (pinfunction "1.27_1.27") (pintype "bidirectional"))
    )
    (net (code "114") (name "unconnected-(H1-Pad1.28)") (class "Default")
      (node (ref "H1") (pin "1.28") (pinfunction "1.28_1.28") (pintype "bidirectional"))
    )
    (net (code "115") (name "unconnected-(H1-Pad1.29)") (class "Default")
      (node (ref "H1") (pin "1.29") (pinfunction "1.29_1.29") (pintype "bidirectional"))
    )
    (net (code "116") (name "unconnected-(H1-Pad1.30)") (class "Default")
      (node (ref "H1") (pin "1.30") (pinfunction "1.30_1.30") (pintype "bidirectional"))
    )
    (net (code "117") (name "unconnected-(H1-Pad1.31)") (class "Default")
      (node (ref "H1") (pin "1.31") (pinfunction "1.31_1.31") (pintype "bidirectional"))
    )
    (net (code "118") (name "unconnected-(H1-Pad1.32)") (class "Default")
      (node (ref "H1") (pin "1.32") (pinfunction "1.32_1.32") (pintype "bidirectional"))
    )
    (net (code "119") (name "unconnected-(H1-Pad1.33)") (class "Default")
      (node (ref "H1") (pin "1.33") (pinfunction "1.33_1.33") (pintype "bidirectional"))
    )
    (net (code "120") (name "unconnected-(H1-Pad1.34)") (class "Default")
      (node (ref "H1") (pin "1.34") (pinfunction "1.34_1.34") (pintype "bidirectional"))
    )
    (net (code "121") (name "unconnected-(H1-Pad1.35)") (class "Default")
      (node (ref "H1") (pin "1.35") (pinfunction "1.35_1.35") (pintype "bidirectional"))
    )
    (net (code "122") (name "unconnected-(H1-Pad1.36)") (class "Default")
      (node (ref "H1") (pin "1.36") (pinfunction "1.36_1.36") (pintype "bidirectional"))
    )
    (net (code "123") (name "unconnected-(H1-Pad1.37)") (class "Default")
      (node (ref "H1") (pin "1.37") (pinfunction "1.37_1.37") (pintype "bidirectional"))
    )
    (net (code "124") (name "unconnected-(H1-Pad1.38)") (class "Default")
      (node (ref "H1") (pin "1.38") (pinfunction "1.38_1.38") (pintype "bidirectional"))
    )
    (net (code "125") (name "unconnected-(H1-Pad1.39)") (class "Default")
      (node (ref "H1") (pin "1.39") (pinfunction "1.39_1.39") (pintype "bidirectional"))
    )
    (net (code "126") (name "unconnected-(H1-Pad1.40)") (class "Default")
      (node (ref "H1") (pin "1.40") (pinfunction "1.40_1.40") (pintype "bidirectional"))
    )
    (net (code "127") (name "unconnected-(H1-Pad1.41)") (class "Default")
      (node (ref "H1") (pin "1.41") (pinfunction "1.41_1.41") (pintype "bidirectional"))
    )
    (net (code "128") (name "unconnected-(H1-Pad1.42)") (class "Default")
      (node (ref "H1") (pin "1.42") (pinfunction "1.42_1.42") (pintype "bidirectional"))
    )
    (net (code "129") (name "unconnected-(H1-Pad1.43)") (class "Default")
      (node (ref "H1") (pin "1.43") (pinfunction "1.43_1.43") (pintype "bidirectional"))
    )
    (net (code "130") (name "unconnected-(H1-Pad1.44)") (class "Default")
      (node (ref "H1") (pin "1.44") (pinfunction "1.44_1.44") (pintype "bidirectional"))
    )
    (net (code "131") (name "unconnected-(H1-Pad1.45)") (class "Default")
      (node (ref "H1") (pin "1.45") (pinfunction "1.45_1.45") (pintype "bidirectional"))
    )
    (net (code "132") (name "unconnected-(H1-Pad1.46)") (class "Default")
      (node (ref "H1") (pin "1.46") (pinfunction "1.46_1.46") (pintype "bidirectional"))
    )
    (net (code "133") (name "unconnected-(H1-Pad1.47)") (class "Default")
      (node (ref "H1") (pin "1.47") (pinfunction "1.47_1.47") (pintype "bidirectional"))
    )
    (net (code "134") (name "unconnected-(H1-Pad1.48)") (class "Default")
      (node (ref "H1") (pin "1.48") (pinfunction "1.48_1.48") (pintype "bidirectional"))
    )
    (net (code "135") (name "unconnected-(H1-Pad1.49)") (class "Default")
      (node (ref "H1") (pin "1.49") (pinfunction "1.49_1.49") (pintype "bidirectional"))
    )
    (net (code "136") (name "unconnected-(H1-Pad1.50)") (class "Default")
      (node (ref "H1") (pin "1.50") (pinfunction "1.50_1.50") (pintype "bidirectional"))
    )
    (net (code "137") (name "unconnected-(H1-Pad1.51)") (class "Default")
      (node (ref "H1") (pin "1.51") (pinfunction "1.51_1.51") (pintype "bidirectional"))
    )
    (net (code "138") (name "unconnected-(H1-Pad1.52)") (class "Default")
      (node (ref "H1") (pin "1.52") (pinfunction "1.52_1.52") (pintype "bidirectional"))
    )
    (net (code "139") (name "unconnected-(H1-Pad2.1)") (class "Default")
      (node (ref "H1") (pin "2.1") (pinfunction "2.1_2.1") (pintype "bidirectional"))
    )
    (net (code "140") (name "unconnected-(H1-Pad2.2)") (class "Default")
      (node (ref "H1") (pin "2.2") (pinfunction "2.2_2.2") (pintype "bidirectional"))
    )
    (net (code "141") (name "unconnected-(H1-Pad2.3)") (class "Default")
      (node (ref "H1") (pin "2.3") (pinfunction "2.3_2.3") (pintype "bidirectional"))
    )
    (net (code "142") (name "unconnected-(H1-Pad2.4)") (class "Default")
      (node (ref "H1") (pin "2.4") (pinfunction "2.4_2.4") (pintype "bidirectional"))
    )
    (net (code "143") (name "unconnected-(H1-Pad2.5)") (class "Default")
      (node (ref "H1") (pin "2.5") (pinfunction "2.5_2.5") (pintype "bidirectional"))
    )
    (net (code "144") (name "unconnected-(H1-Pad2.6)") (class "Default")
      (node (ref "H1") (pin "2.6") (pinfunction "2.6_2.6") (pintype "bidirectional"))
    )
    (net (code "145") (name "unconnected-(H1-Pad2.8)") (class "Default")
      (node (ref "H1") (pin "2.8") (pinfunction "2.8_2.8") (pintype "bidirectional"))
    )
    (net (code "146") (name "unconnected-(H1-Pad2.9)") (class "Default")
      (node (ref "H1") (pin "2.9") (pinfunction "2.9_2.9") (pintype "bidirectional"))
    )
    (net (code "147") (name "unconnected-(H1-Pad2.10)") (class "Default")
      (node (ref "H1") (pin "2.10") (pinfunction "2.10_2.10") (pintype "bidirectional"))
    )
    (net (code "148") (name "unconnected-(H1-Pad2.11)") (class "Default")
      (node (ref "H1") (pin "2.11") (pinfunction "2.11_2.11") (pintype "bidirectional"))
    )
    (net (code "149") (name "unconnected-(H1-Pad2.12)") (class "Default")
      (node (ref "H1") (pin "2.12") (pinfunction "2.12_2.12") (pintype "bidirectional"))
    )
    (net (code "150") (name "unconnected-(H1-Pad2.15)") (class "Default")
      (node (ref "H1") (pin "2.15") (pinfunction "2.15_2.15") (pintype "bidirectional"))
    )
    (net (code "151") (name "unconnected-(H1-Pad2.16)") (class "Default")
      (node (ref "H1") (pin "2.16") (pinfunction "2.16_2.16") (pintype "bidirectional"))
    )
    (net (code "152") (name "unconnected-(H1-Pad2.18)") (class "Default")
      (node (ref "H1") (pin "2.18") (pinfunction "2.18_2.18") (pintype "bidirectional"))
    )
    (net (code "153") (name "unconnected-(H1-Pad2.19)") (class "Default")
      (node (ref "H1") (pin "2.19") (pinfunction "2.19_2.19") (pintype "bidirectional"))
    )
    (net (code "154") (name "unconnected-(H1-Pad2.20)") (class "Default")
      (node (ref "H1") (pin "2.20") (pinfunction "2.20_2.20") (pintype "bidirectional"))
    )
    (net (code "155") (name "unconnected-(H1-Pad2.23)") (class "Default")
      (node (ref "H1") (pin "2.23") (pinfunction "2.23_2.23") (pintype "bidirectional"))
    )
    (net (code "156") (name "unconnected-(H1-Pad2.24)") (class "Default")
      (node (ref "H1") (pin "2.24") (pinfunction "2.24_2.24") (pintype "bidirectional"))
    )
    (net (code "157") (name "unconnected-(H1-Pad2.31)") (class "Default")
      (node (ref "H1") (pin "2.31") (pinfunction "2.31_2.31") (pintype "bidirectional"))
    )
    (net (code "158") (name "unconnected-(H1-Pad2.33)") (class "Default")
      (node (ref "H1") (pin "2.33") (pinfunction "2.33_2.33") (pintype "bidirectional"))
    )
    (net (code "159") (name "unconnected-(H1-Pad2.34)") (class "Default")
      (node (ref "H1") (pin "2.34") (pinfunction "2.34_2.34") (pintype "bidirectional"))
    )
    (net (code "160") (name "unconnected-(H1-Pad2.35)") (class "Default")
      (node (ref "H1") (pin "2.35") (pinfunction "2.35_2.35") (pintype "bidirectional"))
    )
    (net (code "161") (name "unconnected-(H1-Pad2.36)") (class "Default")
      (node (ref "H1") (pin "2.36") (pinfunction "2.36_2.36") (pintype "bidirectional"))
    )
    (net (code "162") (name "unconnected-(H1-Pad2.37)") (class "Default")
      (node (ref "H1") (pin "2.37") (pinfunction "2.37_2.37") (pintype "bidirectional"))
    )
    (net (code "163") (name "unconnected-(H1-Pad2.38)") (class "Default")
      (node (ref "H1") (pin "2.38") (pinfunction "2.38_2.38") (pintype "bidirectional"))
    )
    (net (code "164") (name "unconnected-(H1-Pad2.39)") (class "Default")
      (node (ref "H1") (pin "2.39") (pinfunction "2.39_2.39") (pintype "bidirectional"))
    )
    (net (code "165") (name "unconnected-(H1-Pad2.40)") (class "Default")
      (node (ref "H1") (pin "2.40") (pinfunction "2.40_2.40") (pintype "bidirectional"))
    )
    (net (code "166") (name "unconnected-(H1-Pad2.41)") (class "Default")
      (node (ref "H1") (pin "2.41") (pinfunction "2.41_2.41") (pintype "bidirectional"))
    )
    (net (code "167") (name "unconnected-(H1-Pad2.42)") (class "Default")
      (node (ref "H1") (pin "2.42") (pinfunction "2.42_2.42") (pintype "bidirectional"))
    )
    (net (code "168") (name "unconnected-(H1-Pad2.43)") (class "Default")
      (node (ref "H1") (pin "2.43") (pinfunction "2.43_2.43") (pintype "bidirectional"))
    )
    (net (code "169") (name "unconnected-(H1-Pad2.44)") (class "Default")
      (node (ref "H1") (pin "2.44") (pinfunction "2.44_2.44") (pintype "bidirectional"))
    )
    (net (code "170") (name "unconnected-(H1-Pad2.45)") (class "Default")
      (node (ref "H1") (pin "2.45") (pinfunction "2.45_2.45") (pintype "bidirectional"))
    )
    (net (code "171") (name "unconnected-(H1-Pad2.46)") (class "Default")
      (node (ref "H1") (pin "2.46") (pinfunction "2.46_2.46") (pintype "bidirectional"))
    )
    (net (code "172") (name "unconnected-(H1-Pad2.49)") (class "Default")
      (node (ref "H1") (pin "2.49") (pinfunction "2.49_2.49") (pintype "bidirectional"))
    )
    (net (code "173") (name "unconnected-(H1-Pad2.50)") (class "Default")
      (node (ref "H1") (pin "2.50") (pinfunction "2.50_2.50") (pintype "bidirectional"))
    )
    (net (code "174") (name "unconnected-(H1-Pad2.51)") (class "Default")
      (node (ref "H1") (pin "2.51") (pinfunction "2.51_2.51") (pintype "bidirectional"))
    )
    (net (code "175") (name "unconnected-(H1-Pad2.52)") (class "Default")
      (node (ref "H1") (pin "2.52") (pinfunction "2.52_2.52") (pintype "bidirectional"))
    )
    (net (code "176") (name "unconnected-(H1-PadP$1)") (class "Default")
      (node (ref "H1") (pin "P$1") (pinfunction "P$1_P$1") (pintype "bidirectional"))
    )
    (net (code "177") (name "unconnected-(H1-PadP$2)") (class "Default")
      (node (ref "H1") (pin "P$2") (pinfunction "P$2_P$2") (pintype "bidirectional"))
    )
    (net (code "178") (name "unconnected-(H1-PadP$3)") (class "Default")
      (node (ref "H1") (pin "P$3") (pinfunction "P$3_P$3") (pintype "bidirectional"))
    )
    (net (code "179") (name "unconnected-(JP4-Pad1)") (class "Default")
      (node (ref "JP4") (pin "1") (pinfunction "1_1") (pintype "passive"))
    )
    (net (code "180") (name "unconnected-(P8AB-1-Pad34)") (class "Default")
      (node (ref "P8") (pin "34") (pinfunction "1_34") (pintype "passive"))
    )
    (net (code "181") (name "unconnected-(P8AS-1-Pad8)") (class "Default")
      (node (ref "P8") (pin "8") (pinfunction "1_8") (pintype "passive"))
    )
    (net (code "182") (name "unconnected-(P8AT-1-Pad9)") (class "Default")
      (node (ref "P8") (pin "9") (pinfunction "1_9") (pintype "passive"))
    )
    (net (code "183") (name "unconnected-(P8B-1-Pad10)") (class "Default")
      (node (ref "P8") (pin "10") (pinfunction "1_10") (pintype "passive"))
    )
    (net (code "184") (name "unconnected-(P8E-1-Pad13)") (class "Default")
      (node (ref "P8") (pin "13") (pinfunction "1_13") (pintype "passive"))
    )
    (net (code "185") (name "unconnected-(P8F-1-Pad14)") (class "Default")
      (node (ref "P8") (pin "14") (pinfunction "1_14") (pintype "passive"))
    )
    (net (code "186") (name "unconnected-(P8K-1-Pad19)") (class "Default")
      (node (ref "P8") (pin "19") (pinfunction "1_19") (pintype "passive"))
    )
    (net (code "187") (name "unconnected-(P8O-1-Pad22)") (class "Default")
      (node (ref "P8") (pin "22") (pinfunction "1_22") (pintype "passive"))
    )
    (net (code "188") (name "unconnected-(P9AJ-1-Pad41)") (class "Default")
      (node (ref "P9") (pin "41") (pinfunction "1_41") (pintype "passive"))
    )
    (net (code "189") (name "unconnected-(P9AL-1-Pad43)") (class "Default")
      (node (ref "P9") (pin "43") (pinfunction "1_43") (pintype "passive"))
    )
    (net (code "190") (name "unconnected-(P9AM-1-Pad44)") (class "Default")
      (node (ref "P9") (pin "44") (pinfunction "1_44") (pintype "passive"))
    )
    (net (code "191") (name "unconnected-(P9AN-1-Pad45)") (class "Default")
      (node (ref "P9") (pin "45") (pinfunction "1_45") (pintype "passive"))
    )
    (net (code "192") (name "unconnected-(P9AO-1-Pad46)") (class "Default")
      (node (ref "P9") (pin "46") (pinfunction "1_46") (pintype "passive"))
    )
    (net (code "193") (name "unconnected-(P9AR-1-Pad7)") (class "Default")
      (node (ref "P9") (pin "7") (pinfunction "1_7") (pintype "passive"))
    )
    (net (code "194") (name "unconnected-(P9AS-1-Pad8)") (class "Default")
      (node (ref "P9") (pin "8") (pinfunction "1_8") (pintype "passive"))
    )
    (net (code "195") (name "unconnected-(P9AT-1-Pad9)") (class "Default")
      (node (ref "P9") (pin "9") (pinfunction "1_9") (pintype "passive"))
    )
    (net (code "196") (name "unconnected-(P9F-1-Pad14)") (class "Default")
      (node (ref "P9") (pin "14") (pinfunction "1_14") (pintype "passive"))
    )
    (net (code "197") (name "unconnected-(P9H-1-Pad16)") (class "Default")
      (node (ref "P9") (pin "16") (pinfunction "1_16") (pintype "passive"))
    )
    (net (code "198") (name "unconnected-(P9I-1-Pad17)") (class "Default")
      (node (ref "P9") (pin "17") (pinfunction "1_17") (pintype "passive"))
    )
    (net (code "199") (name "unconnected-(P9J-1-Pad18)") (class "Default")
      (node (ref "P9") (pin "18") (pinfunction "1_18") (pintype "passive"))
    )
    (net (code "200") (name "unconnected-(P9Z-1-Pad32)") (class "Default")
      (node (ref "P9") (pin "32") (pinfunction "1_32") (pintype "passive"))
    )
    (net (code "201") (name "unconnected-(U1-NC-Pad7)") (class "Default")
      (node (ref "U1") (pin "7") (pinfunction "NC_7") (pintype "no_connect"))
    )
    (net (code "202") (name "unconnected-(U1-NC_2-Pad2)") (class "Default")
      (node (ref "U1") (pin "2") (pinfunction "NC_2_2") (pintype "no_connect"))
    )
    (net (code "203") (name "unconnected-(U1-NC_3-Pad3)") (class "Default")
      (node (ref "U1") (pin "3") (pinfunction "NC_3_3") (pintype "no_connect"))
    )
    (net (code "204") (name "unconnected-(U1-NC_4-Pad6)") (class "Default")
      (node (ref "U1") (pin "6") (pinfunction "NC_4_6") (pintype "no_connect"))
    )
    (net (code "205") (name "unconnected-(U5-DIO0-Pad14)") (class "Default")
      (node (ref "U5") (pin "14") (pinfunction "DIO0_14") (pintype "bidirectional"))
    )
    (net (code "206") (name "unconnected-(U5-DIO1-Pad15)") (class "Default")
      (node (ref "U5") (pin "15") (pinfunction "DIO1_15") (pintype "bidirectional"))
    )
    (net (code "207") (name "unconnected-(U5-DIO2-Pad16)") (class "Default")
      (node (ref "U5") (pin "16") (pinfunction "DIO2_16") (pintype "bidirectional"))
    )
    (net (code "208") (name "unconnected-(U5-DIO3-Pad11)") (class "Default")
      (node (ref "U5") (pin "11") (pinfunction "DIO3_11") (pintype "bidirectional"))
    )
    (net (code "209") (name "unconnected-(U5-DIO4-Pad12)") (class "Default")
      (node (ref "U5") (pin "12") (pinfunction "DIO4_12") (pintype "bidirectional"))
    )
    (net (code "210") (name "unconnected-(U5-DIO5-Pad7)") (class "Default")
      (node (ref "U5") (pin "7") (pinfunction "DIO5_7") (pintype "bidirectional"))
    )
    (net (code "211") (name "unconnected-(U6-P$3-Pad3)") (class "Default")
      (node (ref "U6") (pin "3") (pinfunction "P$3_3") (pintype "bidirectional"))
    )
    (net (code "212") (name "unconnected-(U6-P$4-Pad4)") (class "Default")
      (node (ref "U6") (pin "4") (pinfunction "P$4_4") (pintype "bidirectional"))
    )
    (net (code "213") (name "unconnected-(U6-P$5-Pad5)") (class "Default")
      (node (ref "U6") (pin "5") (pinfunction "P$5_5") (pintype "bidirectional"))
    )
    (net (code "214") (name "unconnected-(U6-P$6-Pad6)") (class "Default")
      (node (ref "U6") (pin "6") (pinfunction "P$6_6") (pintype "bidirectional"))
    )
    (net (code "215") (name "unconnected-(U6-P$8-Pad8)") (class "Default")
      (node (ref "U6") (pin "8") (pinfunction "P$8_8") (pintype "bidirectional"))
    )
    (net (code "216") (name "unconnected-(U6-P$10-Pad10)") (class "Default")
      (node (ref "U6") (pin "10") (pinfunction "P$10_10") (pintype "bidirectional"))
    )
    (net (code "217") (name "unconnected-(U6-P$12-Pad12)") (class "Default")
      (node (ref "U6") (pin "12") (pinfunction "P$12_12") (pintype "bidirectional"))
    )
    (net (code "218") (name "unconnected-(U6-P$13-Pad13)") (class "Default")
      (node (ref "U6") (pin "13") (pinfunction "P$13_13") (pintype "bidirectional"))
    )
    (net (code "219") (name "unconnected-(U6-P$14-Pad14)") (class "Default")
      (node (ref "U6") (pin "14") (pinfunction "P$14_14") (pintype "bidirectional"))
    )
    (net (code "220") (name "unconnected-(U6-P$15-Pad15)") (class "Default")
      (node (ref "U6") (pin "15") (pinfunction "P$15_15") (pintype "bidirectional"))
    )
    (net (code "221") (name "unconnected-(U6-P$16-Pad16)") (class "Default")
      (node (ref "U6") (pin "16") (pinfunction "P$16_16") (pintype "bidirectional"))
    )
    (net (code "222") (name "unconnected-(U6-P$17-Pad17)") (class "Default")
      (node (ref "U6") (pin "17") (pinfunction "P$17_17") (pintype "bidirectional"))
    )
    (net (code "223") (name "unconnected-(U6-P$19-Pad19)") (class "Default")
      (node (ref "U6") (pin "19") (pinfunction "P$19_19") (pintype "bidirectional"))
    )
    (net (code "224") (name "unconnected-(U6-P$20-Pad20)") (class "Default")
      (node (ref "U6") (pin "20") (pinfunction "P$20_20") (pintype "bidirectional"))
    )
    (net (code "225") (name "unconnected-(U6-P$22-Pad22)") (class "Default")
      (node (ref "U6") (pin "22") (pinfunction "P$22_22") (pintype "bidirectional"))
    )
    (net (code "226") (name "unconnected-(U6-P$23-Pad23)") (class "Default")
      (node (ref "U6") (pin "23") (pinfunction "P$23_23") (pintype "bidirectional"))
    )
    (net (code "227") (name "unconnected-(U6-P$24-Pad24)") (class "Default")
      (node (ref "U6") (pin "24") (pinfunction "P$24_24") (pintype "bidirectional"))
    )
    (net (code "228") (name "unconnected-(U6-P$25-Pad25)") (class "Default")
      (node (ref "U6") (pin "25") (pinfunction "P$25_25") (pintype "bidirectional"))
    )
    (net (code "229") (name "unconnected-(U6-P$26-Pad26)") (class "Default")
      (node (ref "U6") (pin "26") (pinfunction "P$26_26") (pintype "bidirectional"))
    )
    (net (code "230") (name "unconnected-(U6-P$27-Pad27)") (class "Default")
      (node (ref "U6") (pin "27") (pinfunction "P$27_27") (pintype "bidirectional"))
    )
    (net (code "231") (name "unconnected-(U6-P$28-Pad28)") (class "Default")
      (node (ref "U6") (pin "28") (pinfunction "P$28_28") (pintype "bidirectional"))
    )
    (net (code "232") (name "unconnected-(U6-P$29-Pad29)") (class "Default")
      (node (ref "U6") (pin "29") (pinfunction "P$29_29") (pintype "bidirectional"))
    )
    (net (code "233") (name "unconnected-(U6-P$30-Pad30)") (class "Default")
      (node (ref "U6") (pin "30") (pinfunction "P$30_30") (pintype "bidirectional"))
    )
    (net (code "234") (name "unconnected-(U6-P$31-Pad31)") (class "Default")
      (node (ref "U6") (pin "31") (pinfunction "P$31_31") (pintype "bidirectional"))
    )
    (net (code "235") (name "unconnected-(U6-P$33-Pad33)") (class "Default")
      (node (ref "U6") (pin "33") (pinfunction "P$33_33") (pintype "bidirectional"))
    )
    (net (code "236") (name "unconnected-(U6-P$34-Pad34)") (class "Default")
      (node (ref "U6") (pin "34") (pinfunction "P$34_34") (pintype "bidirectional"))
    )
    (net (code "237") (name "unconnected-(U6-P$35-Pad35)") (class "Default")
      (node (ref "U6") (pin "35") (pinfunction "P$35_35") (pintype "bidirectional"))
    )
    (net (code "238") (name "unconnected-(U6-P$36-Pad36)") (class "Default")
      (node (ref "U6") (pin "36") (pinfunction "P$36_36") (pintype "bidirectional"))
    )
    (net (code "239") (name "unconnected-(U6-P$37-Pad37)") (class "Default")
      (node (ref "U6") (pin "37") (pinfunction "P$37_37") (pintype "bidirectional"))
    )
    (net (code "240") (name "unconnected-(U6-P$38-Pad38)") (class "Default")
      (node (ref "U6") (pin "38") (pinfunction "P$38_38") (pintype "bidirectional"))
    )
    (net (code "241") (name "unconnected-(U6-P$39-Pad39)") (class "Default")
      (node (ref "U6") (pin "39") (pinfunction "P$39_39") (pintype "bidirectional"))
    )
    (net (code "242") (name "unconnected-(U6-P$40-Pad40)") (class "Default")
      (node (ref "U6") (pin "40") (pinfunction "P$40_40") (pintype "bidirectional"))
    )
    (net (code "243") (name "unconnected-(U6-P$41-Pad41)") (class "Default")
      (node (ref "U6") (pin "41") (pinfunction "P$41_41") (pintype "bidirectional"))
    )
    (net (code "244") (name "unconnected-(U6-P$43-Pad43)") (class "Default")
      (node (ref "U6") (pin "43") (pinfunction "P$43_43") (pintype "bidirectional"))
    )
    (net (code "245") (name "unconnected-(U6-P$45-Pad45)") (class "Default")
      (node (ref "U6") (pin "45") (pinfunction "P$45_45") (pintype "bidirectional"))
    )
    (net (code "246") (name "unconnected-(U6-P$46-Pad46)") (class "Default")
      (node (ref "U6") (pin "46") (pinfunction "P$46_46") (pintype "bidirectional"))
    )
    (net (code "247") (name "unconnected-(U6-P$47-Pad47)") (class "Default")
      (node (ref "U6") (pin "47") (pinfunction "P$47_47") (pintype "bidirectional"))
    )
    (net (code "248") (name "unconnected-(U6-P$48-Pad48)") (class "Default")
      (node (ref "U6") (pin "48") (pinfunction "P$48_48") (pintype "bidirectional"))
    )
    (net (code "249") (name "unconnected-(U6-P$49-Pad49)") (class "Default")
      (node (ref "U6") (pin "49") (pinfunction "P$49_49") (pintype "bidirectional"))
    )
    (net (code "250") (name "unconnected-(U6-P$50-Pad50)") (class "Default")
      (node (ref "U6") (pin "50") (pinfunction "P$50_50") (pintype "bidirectional"))
    )
    (net (code "251") (name "unconnected-(U6-P$51-Pad51)") (class "Default")
      (node (ref "U6") (pin "51") (pinfunction "P$51_51") (pintype "bidirectional"))
    )
    (net (code "252") (name "unconnected-(U6-P$52-Pad52)") (class "Default")
      (node (ref "U6") (pin "52") (pinfunction "P$52_52") (pintype "bidirectional"))
    )
    (net (code "253") (name "unconnected-(U6-P$53-Pad53)") (class "Default")
      (node (ref "U6") (pin "53") (pinfunction "P$53_53") (pintype "bidirectional"))
    )
    (net (code "254") (name "unconnected-(U6-P$54-Pad54)") (class "Default")
      (node (ref "U6") (pin "54") (pinfunction "P$54_54") (pintype "bidirectional"))
    )
    (net (code "255") (name "unconnected-(U6-P$55-Pad55)") (class "Default")
      (node (ref "U6") (pin "55") (pinfunction "P$55_55") (pintype "bidirectional"))
    )
    (net (code "256") (name "unconnected-(U6-P$56-Pad56)") (class "Default")
      (node (ref "U6") (pin "56") (pinfunction "P$56_56") (pintype "bidirectional"))
    )
    (net (code "257") (name "unconnected-(U6-P$57-Pad57)") (class "Default")
      (node (ref "U6") (pin "57") (pinfunction "P$57_57") (pintype "bidirectional"))
    )
    (net (code "258") (name "unconnected-(U6-P$58-Pad58)") (class "Default")
      (node (ref "U6") (pin "58") (pinfunction "P$58_58") (pintype "bidirectional"))
    )
    (net (code "259") (name "unconnected-(U6-P$59-Pad59)") (class "Default")
      (node (ref "U6") (pin "59") (pinfunction "P$59_59") (pintype "bidirectional"))
    )
    (net (code "260") (name "unconnected-(U6-P$60-Pad60)") (class "Default")
      (node (ref "U6") (pin "60") (pinfunction "P$60_60") (pintype "bidirectional"))
    )
    (net (code "261") (name "unconnected-(U6-P$61-Pad61)") (class "Default")
      (node (ref "U6") (pin "61") (pinfunction "P$61_61") (pintype "bidirectional"))
    )
    (net (code "262") (name "unconnected-(U6-P$62-Pad62)") (class "Default")
      (node (ref "U6") (pin "62") (pinfunction "P$62_62") (pintype "bidirectional"))
    )
    (net (code "263") (name "unconnected-(U6-P$63-Pad63)") (class "Default")
      (node (ref "U6") (pin "63") (pinfunction "P$63_63") (pintype "bidirectional"))
    )
    (net (code "264") (name "unconnected-(U6-P$65-Pad65)") (class "Default")
      (node (ref "U6") (pin "65") (pinfunction "P$65_65") (pintype "bidirectional"))
    )
    (net (code "265") (name "unconnected-(U6-P$66-Pad66)") (class "Default")
      (node (ref "U6") (pin "66") (pinfunction "P$66_66") (pintype "bidirectional"))
    )
    (net (code "266") (name "unconnected-(U6-P$67-Pad67)") (class "Default")
      (node (ref "U6") (pin "67") (pinfunction "P$67_67") (pintype "bidirectional"))
    )
    (net (code "267") (name "unconnected-(U6-P$68-Pad68)") (class "Default")
      (node (ref "U6") (pin "68") (pinfunction "P$68_68") (pintype "bidirectional"))
    )
    (net (code "268") (name "unconnected-(U6-P$69-Pad69)") (class "Default")
      (node (ref "U6") (pin "69") (pinfunction "P$69_69") (pintype "bidirectional"))
    )
    (net (code "269") (name "unconnected-(X1-P$1-Pad1)") (class "Default")
      (node (ref "X1") (pin "1") (pinfunction "P$1_1") (pintype "bidirectional"))
    )
    (net (code "270") (name "unconnected-(X1-P$4-Pad4)") (class "Default")
      (node (ref "X1") (pin "4") (pinfunction "P$4_4") (pintype "bidirectional"))
    )
    (net (code "271") (name "unconnected-(X1-P$6-Pad6)") (class "Default")
      (node (ref "X1") (pin "6") (pinfunction "P$6_6") (pintype "bidirectional"))
    )
    (net (code "272") (name "unconnected-(X1-P$7-Pad7)") (class "Default")
      (node (ref "X1") (pin "7") (pinfunction "P$7_7") (pintype "bidirectional"))
    )
    (net (code "273") (name "unconnected-(X1-P$9-Pad9)") (class "Default")
      (node (ref "X1") (pin "9") (pinfunction "P$9_9") (pintype "bidirectional"))
    )
    (net (code "274") (name "unconnected-(X1-P$12-Pad12)") (class "Default")
      (node (ref "X1") (pin "12") (pinfunction "P$12_12") (pintype "bidirectional"))
    )
    (net (code "275") (name "unconnected-(X1-P$14-Pad14)") (class "Default")
      (node (ref "X1") (pin "14") (pinfunction "P$14_14") (pintype "bidirectional"))
    )
    (net (code "276") (name "unconnected-(X1-P$17-Pad17)") (class "Default")
      (node (ref "X1") (pin "17") (pinfunction "P$17_17") (pintype "bidirectional"))
    )
    (net (code "277") (name "unconnected-(X1-P$20-Pad20)") (class "Default")
      (node (ref "X1") (pin "20") (pinfunction "P$20_20") (pintype "bidirectional"))
    )
    (net (code "278") (name "unconnected-(X1-P$25-Pad25)") (class "Default")
      (node (ref "X1") (pin "25") (pinfunction "P$25_25") (pintype "bidirectional"))
    )
    (net (code "279") (name "unconnected-(X1-P$27-Pad27)") (class "Default")
      (node (ref "X1") (pin "27") (pinfunction "P$27_27") (pintype "bidirectional"))
    )
    (net (code "280") (name "unconnected-(X1-P$28-Pad28)") (class "Default")
      (node (ref "X1") (pin "28") (pinfunction "P$28_28") (pintype "bidirectional"))
    )
    (net (code "281") (name "unconnected-(X1-P$29-Pad29)") (class "Default")
      (node (ref "X1") (pin "29") (pinfunction "P$29_29") (pintype "bidirectional"))
    )
    (net (code "282") (name "unconnected-(X1-P$30-Pad30)") (class "Default")
      (node (ref "X1") (pin "30") (pinfunction "P$30_30") (pintype "bidirectional"))
    )
    (net (code "283") (name "unconnected-(X1-P$31-Pad31)") (class "Default")
      (node (ref "X1") (pin "31") (pinfunction "P$31_31") (pintype "bidirectional"))
    )
    (net (code "284") (name "unconnected-(X1-P$32-Pad32)") (class "Default")
      (node (ref "X1") (pin "32") (pinfunction "P$32_32") (pintype "bidirectional"))
    )
    (net (code "285") (name "unconnected-(X1-P$33-Pad33)") (class "Default")
      (node (ref "X1") (pin "33") (pinfunction "P$33_33") (pintype "bidirectional"))
    )
    (net (code "286") (name "unconnected-(X1-P$34-Pad34)") (class "Default")
      (node (ref "X1") (pin "34") (pinfunction "P$34_34") (pintype "bidirectional"))
    )
    (net (code "287") (name "unconnected-(X1-P$35-Pad35)") (class "Default")
      (node (ref "X1") (pin "35") (pinfunction "P$35_35") (pintype "bidirectional"))
    )
    (net (code "288") (name "unconnected-(X1-P$36-Pad36)") (class "Default")
      (node (ref "X1") (pin "36") (pinfunction "P$36_36") (pintype "bidirectional"))
    )
    (net (code "289") (name "unconnected-(X1-P$37-Pad37)") (class "Default")
      (node (ref "X1") (pin "37") (pinfunction "P$37_37") (pintype "bidirectional"))
    )
    (net (code "290") (name "unconnected-(X1-P$38-Pad38)") (class "Default")
      (node (ref "X1") (pin "38") (pinfunction "P$38_38") (pintype "bidirectional"))
    )
    (net (code "291") (name "unconnected-(X1-P$40-Pad40)") (class "Default")
      (node (ref "X1") (pin "40") (pinfunction "P$40_40") (pintype "bidirectional"))
    )
    (net (code "292") (name "unconnected-(X2-Pad1)") (class "Default")
      (node (ref "X2") (pin "1") (pinfunction "1_1") (pintype "passive"))
    )
    (net (code "293") (name "unconnected-(X2AA-1-Pad33)") (class "Default")
      (node (ref "X2") (pin "33") (pinfunction "1_33") (pintype "passive"))
    )
    (net (code "294") (name "unconnected-(X2AB-1-Pad34)") (class "Default")
      (node (ref "X2") (pin "34") (pinfunction "1_34") (pintype "passive"))
    )
    (net (code "295") (name "unconnected-(X2AC-1-Pad35)") (class "Default")
      (node (ref "X2") (pin "35") (pinfunction "1_35") (pintype "passive"))
    )
    (net (code "296") (name "unconnected-(X2AD-1-Pad36)") (class "Default")
      (node (ref "X2") (pin "36") (pinfunction "1_36") (pintype "passive"))
    )
    (net (code "297") (name "unconnected-(X2AE-1-Pad37)") (class "Default")
      (node (ref "X2") (pin "37") (pinfunction "1_37") (pintype "passive"))
    )
    (net (code "298") (name "unconnected-(X2AF-1-Pad38)") (class "Default")
      (node (ref "X2") (pin "38") (pinfunction "1_38") (pintype "passive"))
    )
    (net (code "299") (name "unconnected-(X2AG-1-Pad39)") (class "Default")
      (node (ref "X2") (pin "39") (pinfunction "1_39") (pintype "passive"))
    )
    (net (code "300") (name "unconnected-(X2AH-1-Pad4)") (class "Default")
      (node (ref "X2") (pin "4") (pinfunction "1_4") (pintype "passive"))
    )
    (net (code "301") (name "unconnected-(X2AI-1-Pad40)") (class "Default")
      (node (ref "X2") (pin "40") (pinfunction "1_40") (pintype "passive"))
    )
    (net (code "302") (name "unconnected-(X2AJ-1-Pad5)") (class "Default")
      (node (ref "X2") (pin "5") (pinfunction "1_5") (pintype "passive"))
    )
    (net (code "303") (name "unconnected-(X2AK-1-Pad6)") (class "Default")
      (node (ref "X2") (pin "6") (pinfunction "1_6") (pintype "passive"))
    )
    (net (code "304") (name "unconnected-(X2AL-1-Pad7)") (class "Default")
      (node (ref "X2") (pin "7") (pinfunction "1_7") (pintype "passive"))
    )
    (net (code "305") (name "unconnected-(X2AM-1-Pad8)") (class "Default")
      (node (ref "X2") (pin "8") (pinfunction "1_8") (pintype "passive"))
    )
    (net (code "306") (name "unconnected-(X2AN-1-Pad9)") (class "Default")
      (node (ref "X2") (pin "9") (pinfunction "1_9") (pintype "passive"))
    )
    (net (code "307") (name "unconnected-(X2B-1-Pad10)") (class "Default")
      (node (ref "X2") (pin "10") (pinfunction "1_10") (pintype "passive"))
    )
    (net (code "308") (name "unconnected-(X2C-1-Pad11)") (class "Default")
      (node (ref "X2") (pin "11") (pinfunction "1_11") (pintype "passive"))
    )
    (net (code "309") (name "unconnected-(X2D-1-Pad12)") (class "Default")
      (node (ref "X2") (pin "12") (pinfunction "1_12") (pintype "passive"))
    )
    (net (code "310") (name "unconnected-(X2E-1-Pad13)") (class "Default")
      (node (ref "X2") (pin "13") (pinfunction "1_13") (pintype "passive"))
    )
    (net (code "311") (name "unconnected-(X2F-1-Pad14)") (class "Default")
      (node (ref "X2") (pin "14") (pinfunction "1_14") (pintype "passive"))
    )
    (net (code "312") (name "unconnected-(X2G-1-Pad15)") (class "Default")
      (node (ref "X2") (pin "15") (pinfunction "1_15") (pintype "passive"))
    )
    (net (code "313") (name "unconnected-(X2H-1-Pad16)") (class "Default")
      (node (ref "X2") (pin "16") (pinfunction "1_16") (pintype "passive"))
    )
    (net (code "314") (name "unconnected-(X2I-1-Pad17)") (class "Default")
      (node (ref "X2") (pin "17") (pinfunction "1_17") (pintype "passive"))
    )
    (net (code "315") (name "unconnected-(X2J-1-Pad18)") (class "Default")
      (node (ref "X2") (pin "18") (pinfunction "1_18") (pintype "passive"))
    )
    (net (code "316") (name "unconnected-(X2K-1-Pad19)") (class "Default")
      (node (ref "X2") (pin "19") (pinfunction "1_19") (pintype "passive"))
    )
    (net (code "317") (name "unconnected-(X2L-1-Pad2)") (class "Default")
      (node (ref "X2") (pin "2") (pinfunction "1_2") (pintype "passive"))
    )
    (net (code "318") (name "unconnected-(X2M-1-Pad20)") (class "Default")
      (node (ref "X2") (pin "20") (pinfunction "1_20") (pintype "passive"))
    )
    (net (code "319") (name "unconnected-(X2N-1-Pad21)") (class "Default")
      (node (ref "X2") (pin "21") (pinfunction "1_21") (pintype "passive"))
    )
    (net (code "320") (name "unconnected-(X2O-1-Pad22)") (class "Default")
      (node (ref "X2") (pin "22") (pinfunction "1_22") (pintype "passive"))
    )
    (net (code "321") (name "unconnected-(X2P-1-Pad23)") (class "Default")
      (node (ref "X2") (pin "23") (pinfunction "1_23") (pintype "passive"))
    )
    (net (code "322") (name "unconnected-(X2Q-1-Pad24)") (class "Default")
      (node (ref "X2") (pin "24") (pinfunction "1_24") (pintype "passive"))
    )
    (net (code "323") (name "unconnected-(X2R-1-Pad25)") (class "Default")
      (node (ref "X2") (pin "25") (pinfunction "1_25") (pintype "passive"))
    )
    (net (code "324") (name "unconnected-(X2S-1-Pad26)") (class "Default")
      (node (ref "X2") (pin "26") (pinfunction "1_26") (pintype "passive"))
    )
    (net (code "325") (name "unconnected-(X2T-1-Pad27)") (class "Default")
      (node (ref "X2") (pin "27") (pinfunction "1_27") (pintype "passive"))
    )
    (net (code "326") (name "unconnected-(X2U-1-Pad28)") (class "Default")
      (node (ref "X2") (pin "28") (pinfunction "1_28") (pintype "passive"))
    )
    (net (code "327") (name "unconnected-(X2V-1-Pad29)") (class "Default")
      (node (ref "X2") (pin "29") (pinfunction "1_29") (pintype "passive"))
    )
    (net (code "328") (name "unconnected-(X2W-1-Pad3)") (class "Default")
      (node (ref "X2") (pin "3") (pinfunction "1_3") (pintype "passive"))
    )
    (net (code "329") (name "unconnected-(X2X-1-Pad30)") (class "Default")
      (node (ref "X2") (pin "30") (pinfunction "1_30") (pintype "passive"))
    )
    (net (code "330") (name "unconnected-(X2Y-1-Pad31)") (class "Default")
      (node (ref "X2") (pin "31") (pinfunction "1_31") (pintype "passive"))
    )
    (net (code "331") (name "unconnected-(X2Z-1-Pad32)") (class "Default")
      (node (ref "X2") (pin "32") (pinfunction "1_32") (pintype "passive"))
    )
  )
)
